# EDR.net
KiCad netlist of a schematic drawn in Altium Designer
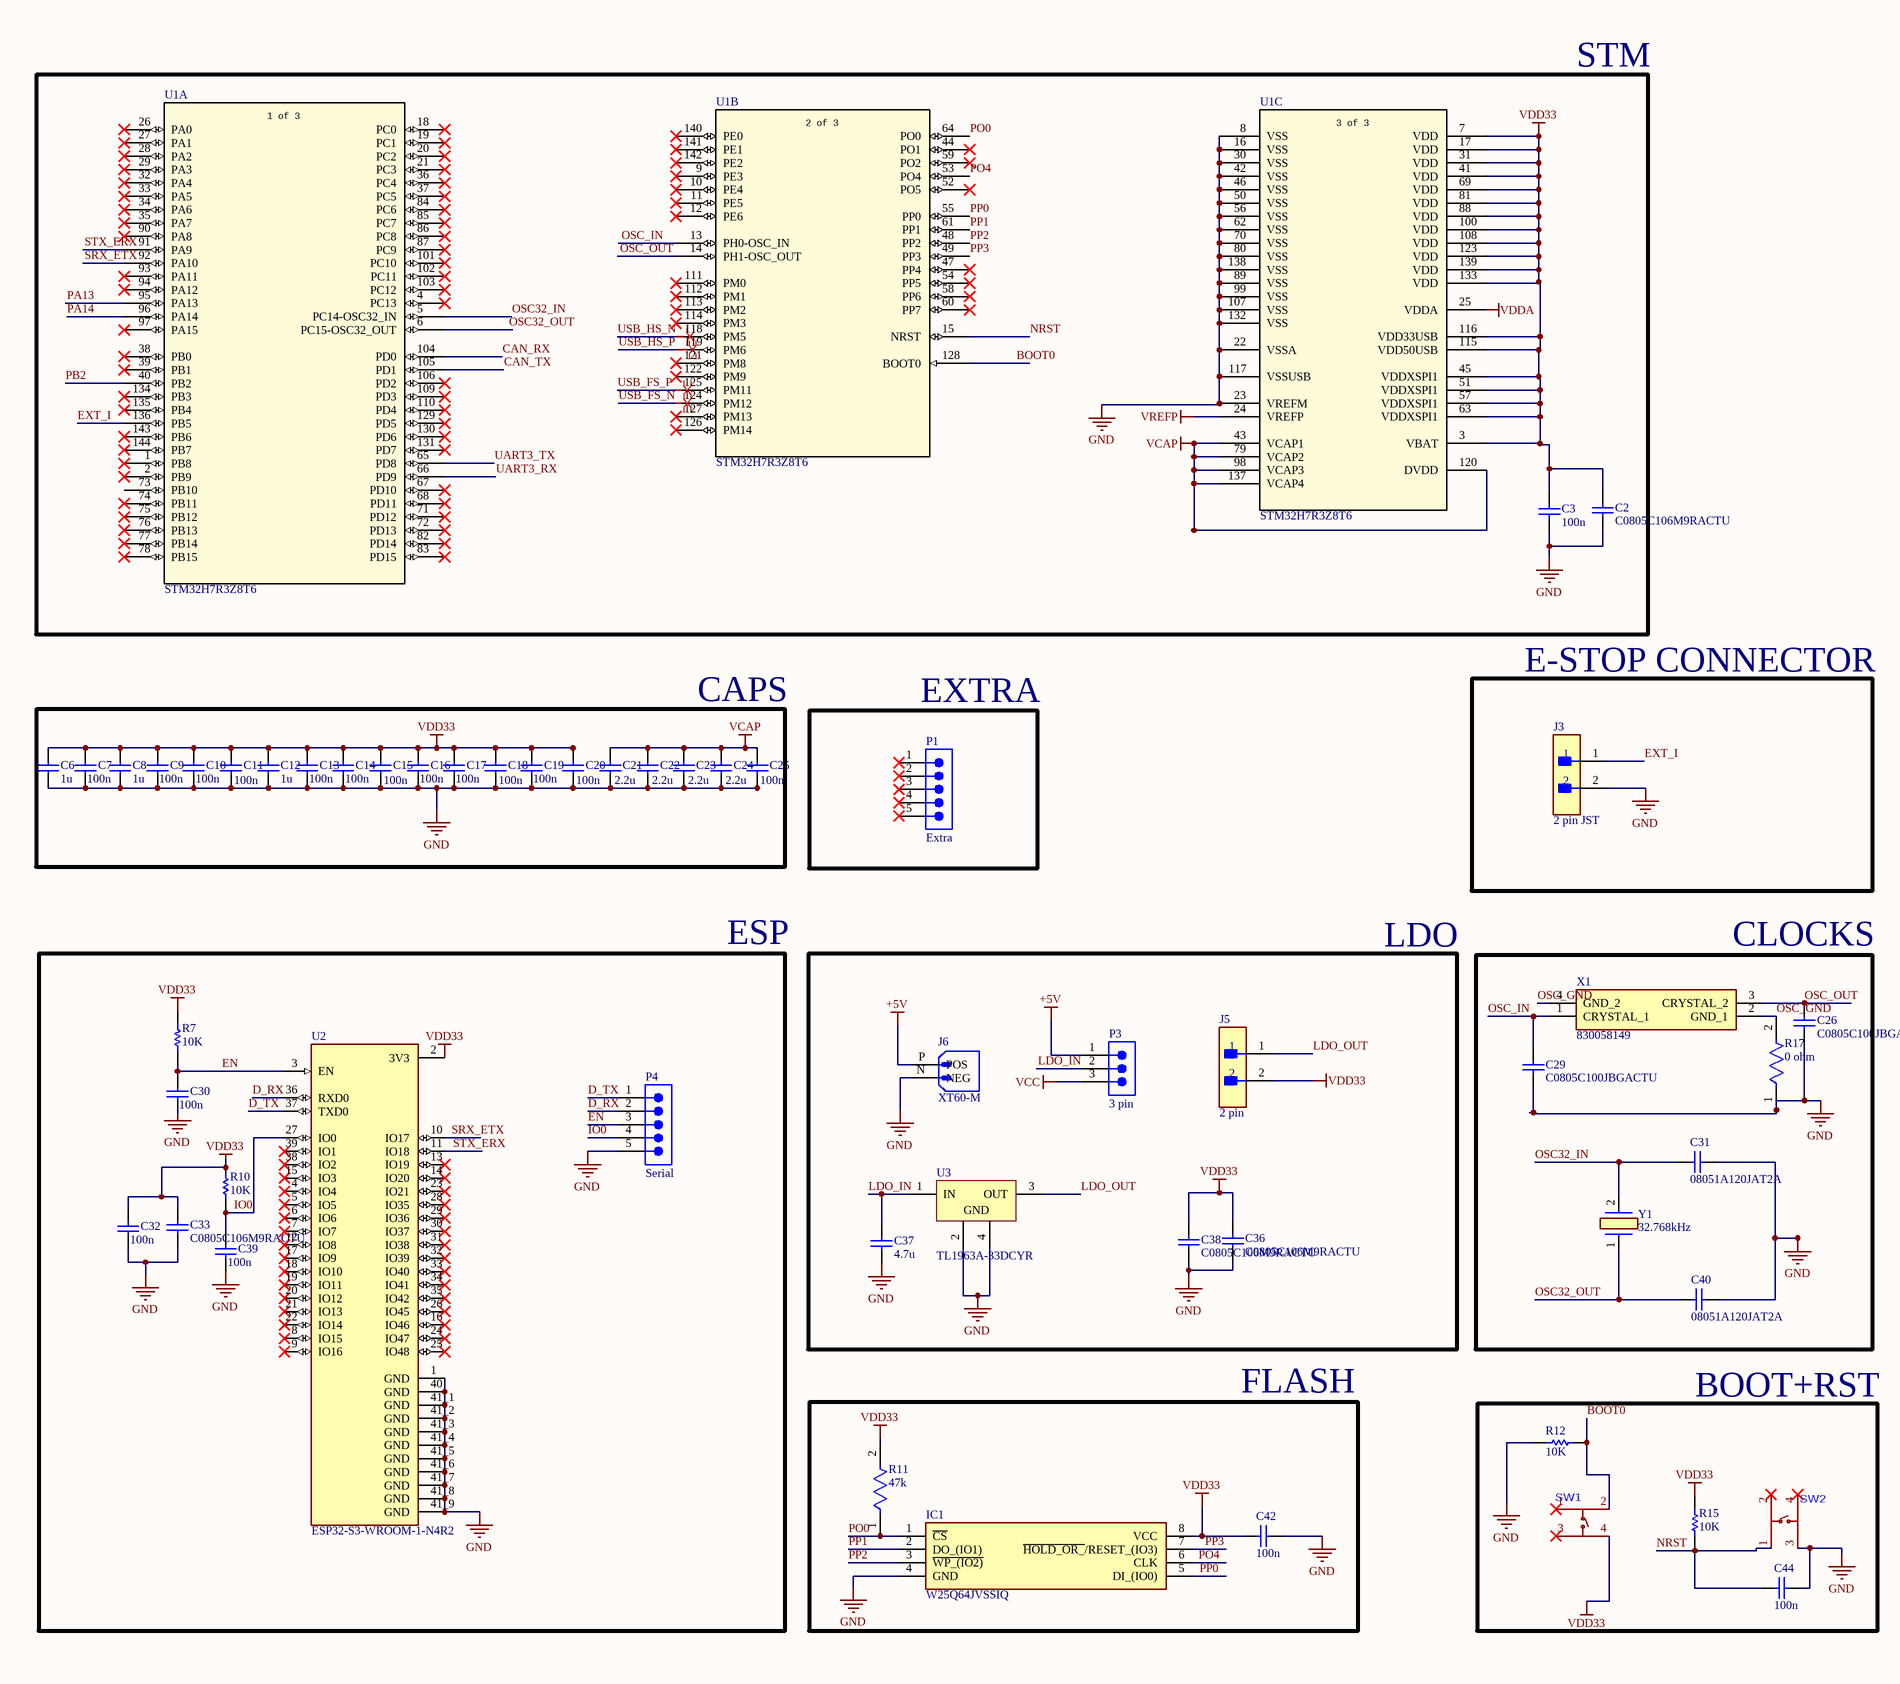
[diagram p0: EDR.SchDoc, left]
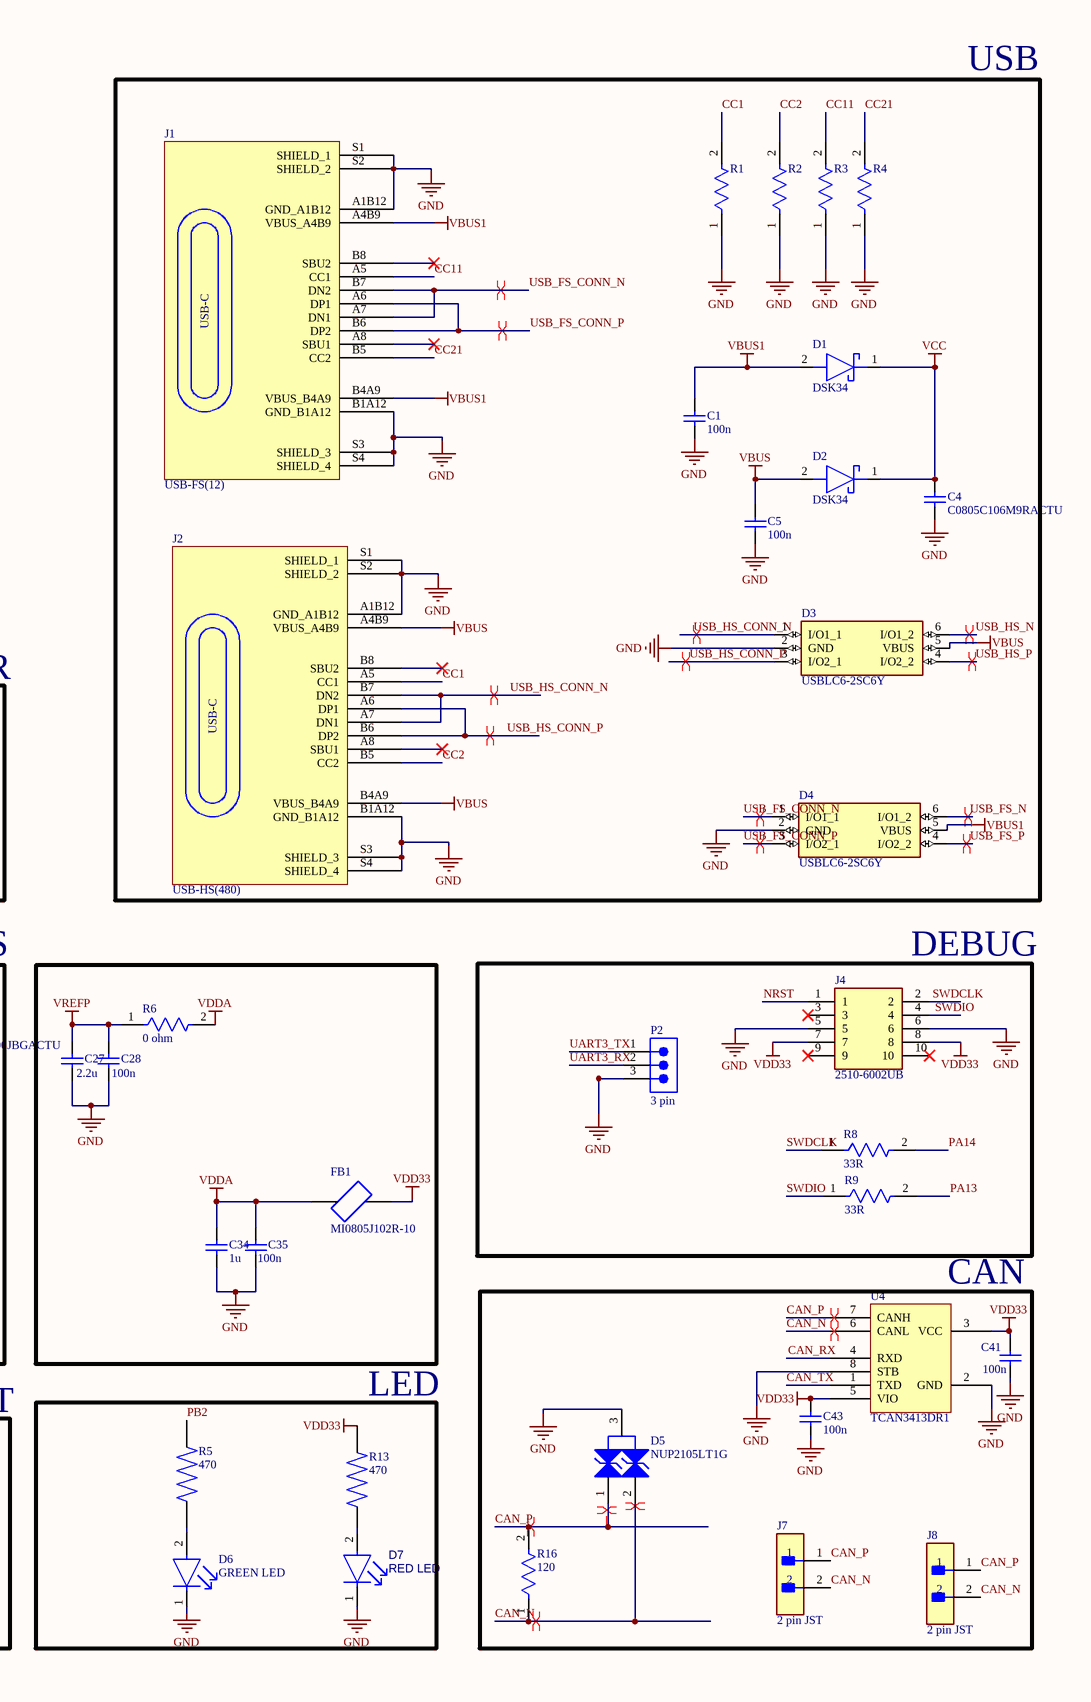
[diagram p1: EDR.SchDoc, right]

(export (version "E")
  (design (tool "Eeschema 10.0.6"))
  (components
    (comp (ref "C1")
      (value "100n")
      (footprint "CAPC2013X145X48ML20T23")
      (description "0.1uF")
      (fields (field (name "PART NUMBER") "VJ0805Y104MXAMT") (field (name "MANUFACTURER") "Vitramon"))
      (libsource (lib "Schlib1") (part "CMP-2007-01796-1"))
    )
    (comp (ref "C2")
      (value "C0805C106M9RACTU")
      (footprint "CAPC2013X145X50ML20T25")
      (description "10uF")
      (fields (field (name "MANUFACTURER") "Kemet") (field (name "LCSC PART NUMBER") "C1710"))
      (libsource (lib "Schlib1") (part "CMP-2007-01213-1"))
    )
    (comp (ref "C3")
      (value "100n")
      (footprint "CAPC2013X145X48ML20T23")
      (description "0.1uF")
      (fields (field (name "PART NUMBER") "VJ0805Y104MXAMT") (field (name "MANUFACTURER") "Vitramon"))
      (libsource (lib "Schlib1") (part "CMP-2007-01796-1"))
    )
    (comp (ref "C4")
      (value "C0805C106M9RACTU")
      (footprint "CAPC2013X145X50ML20T25")
      (description "10uF")
      (fields (field (name "MANUFACTURER") "Kemet") (field (name "LCSC PART NUMBER") "C1710"))
      (libsource (lib "Schlib1") (part "CMP-2007-01213-1"))
    )
    (comp (ref "C5")
      (value "100n")
      (footprint "CAPC2013X145X48ML20T23")
      (description "0.1uF")
      (fields (field (name "PART NUMBER") "VJ0805Y104MXAMT") (field (name "MANUFACTURER") "Vitramon"))
      (libsource (lib "Schlib1") (part "CMP-2007-01796-1"))
    )
    (comp (ref "C6")
      (value "1u")
      (footprint "CAPC2013X145X50ML20T20")
      (description "1uF")
      (fields (field (name "PART NUMBER") "VJ0805Y105KXQRW1BC") (field (name "MANUFACTURER") "Vitramon"))
      (libsource (lib "Schlib1") (part "CMP-2007-01676-1"))
    )
    (comp (ref "C7")
      (value "100n")
      (footprint "CAPC2013X145X48ML20T23")
      (description "0.1uF")
      (fields (field (name "PART NUMBER") "VJ0805Y104MXAMT") (field (name "MANUFACTURER") "Vitramon"))
      (libsource (lib "Schlib1") (part "CMP-2007-01796-1"))
    )
    (comp (ref "C8")
      (value "1u")
      (footprint "CAPC2013X145X50ML20T20")
      (description "1uF")
      (fields (field (name "PART NUMBER") "VJ0805Y105KXQRW1BC") (field (name "MANUFACTURER") "Vitramon"))
      (libsource (lib "Schlib1") (part "CMP-2007-01676-1"))
    )
    (comp (ref "C9")
      (value "100n")
      (footprint "CAPC2013X145X48ML20T23")
      (description "0.1uF")
      (fields (field (name "PART NUMBER") "VJ0805Y104MXAMT") (field (name "MANUFACTURER") "Vitramon"))
      (libsource (lib "Schlib1") (part "CMP-2007-01796-1"))
    )
    (comp (ref "C10")
      (value "100n")
      (footprint "CAPC2013X145X48ML20T23")
      (description "0.1uF")
      (fields (field (name "PART NUMBER") "VJ0805Y104MXAMT") (field (name "MANUFACTURER") "Vitramon"))
      (libsource (lib "Schlib1") (part "CMP-2007-01796-1"))
    )
    (comp (ref "C11")
      (value "100n")
      (footprint "CAPC2013X145X48ML20T23")
      (description "0.1uF")
      (fields (field (name "PART NUMBER") "VJ0805Y104MXAMT") (field (name "MANUFACTURER") "Vitramon"))
      (libsource (lib "Schlib1") (part "CMP-2007-01796-1"))
    )
    (comp (ref "C12")
      (value "1u")
      (footprint "CAPC2013X145X50ML20T20")
      (description "1uF")
      (fields (field (name "PART NUMBER") "VJ0805Y105KXQRW1BC") (field (name "MANUFACTURER") "Vitramon"))
      (libsource (lib "Schlib1") (part "CMP-2007-01676-1"))
    )
    (comp (ref "C13")
      (value "100n")
      (footprint "CAPC2013X145X48ML20T23")
      (description "0.1uF")
      (fields (field (name "PART NUMBER") "VJ0805Y104MXAMT") (field (name "MANUFACTURER") "Vitramon"))
      (libsource (lib "Schlib1") (part "CMP-2007-01796-1"))
    )
    (comp (ref "C14")
      (value "100n")
      (footprint "CAPC2013X145X48ML20T23")
      (description "0.1uF")
      (fields (field (name "PART NUMBER") "VJ0805Y104MXAMT") (field (name "MANUFACTURER") "Vitramon"))
      (libsource (lib "Schlib1") (part "CMP-2007-01796-1"))
    )
    (comp (ref "C15")
      (value "100n")
      (footprint "CAPC2013X145X48ML20T23")
      (description "0.1uF")
      (fields (field (name "PART NUMBER") "VJ0805Y104MXAMT") (field (name "MANUFACTURER") "Vitramon"))
      (libsource (lib "Schlib1") (part "CMP-2007-01796-1"))
    )
    (comp (ref "C16")
      (value "100n")
      (footprint "CAPC2013X145X48ML20T23")
      (description "0.1uF")
      (fields (field (name "PART NUMBER") "VJ0805Y104MXAMT") (field (name "MANUFACTURER") "Vitramon"))
      (libsource (lib "Schlib1") (part "CMP-2007-01796-1"))
    )
    (comp (ref "C17")
      (value "100n")
      (footprint "CAPC2013X145X48ML20T23")
      (description "0.1uF")
      (fields (field (name "PART NUMBER") "VJ0805Y104MXAMT") (field (name "MANUFACTURER") "Vitramon"))
      (libsource (lib "Schlib1") (part "CMP-2007-01796-1"))
    )
    (comp (ref "C18")
      (value "100n")
      (footprint "CAPC2013X145X48ML20T23")
      (description "0.1uF")
      (fields (field (name "PART NUMBER") "VJ0805Y104MXAMT") (field (name "MANUFACTURER") "Vitramon"))
      (libsource (lib "Schlib1") (part "CMP-2007-01796-1"))
    )
    (comp (ref "C19")
      (value "100n")
      (footprint "CAPC2013X145X48ML20T23")
      (description "0.1uF")
      (fields (field (name "PART NUMBER") "VJ0805Y104MXAMT") (field (name "MANUFACTURER") "Vitramon"))
      (libsource (lib "Schlib1") (part "CMP-2007-01796-1"))
    )
    (comp (ref "C20")
      (value "100n")
      (footprint "CAPC2013X145X48ML20T23")
      (description "0.1uF")
      (fields (field (name "PART NUMBER") "VJ0805Y104MXAMT") (field (name "MANUFACTURER") "Vitramon"))
      (libsource (lib "Schlib1") (part "CMP-2007-01796-1"))
    )
    (comp (ref "C21")
      (value "2.2u")
      (footprint "CAPC2013X140X50ML20T25")
      (description "2.2uF")
      (fields (field (name "PART NUMBER") "C0805X225K8RACTU") (field (name "MANUFACTURER") "Kemet"))
      (libsource (lib "Schlib1") (part "CMP-2007-03314-1"))
    )
    (comp (ref "C22")
      (value "2.2u")
      (footprint "CAPC2013X140X50ML20T25")
      (description "2.2uF")
      (fields (field (name "PART NUMBER") "C0805X225K8RACTU") (field (name "MANUFACTURER") "Kemet"))
      (libsource (lib "Schlib1") (part "CMP-2007-03314-1"))
    )
    (comp (ref "C23")
      (value "2.2u")
      (footprint "CAPC2013X140X50ML20T25")
      (description "2.2uF")
      (fields (field (name "PART NUMBER") "C0805X225K8RACTU") (field (name "MANUFACTURER") "Kemet"))
      (libsource (lib "Schlib1") (part "CMP-2007-03314-1"))
    )
    (comp (ref "C24")
      (value "2.2u")
      (footprint "CAPC2013X140X50ML20T25")
      (description "2.2uF")
      (fields (field (name "PART NUMBER") "C0805X225K8RACTU") (field (name "MANUFACTURER") "Kemet"))
      (libsource (lib "Schlib1") (part "CMP-2007-03314-1"))
    )
    (comp (ref "C25")
      (value "100n")
      (footprint "CAPC2013X145X48ML20T23")
      (description "0.1uF")
      (fields (field (name "PART NUMBER") "VJ0805Y104MXAMT") (field (name "MANUFACTURER") "Vitramon"))
      (libsource (lib "Schlib1") (part "CMP-2007-01796-1"))
    )
    (comp (ref "C26")
      (value "C0805C100JBGACTU")
      (footprint "CAPC1608X92X38NL15T08")
      (description "10pF")
      (fields (field (name "MANUFACTURER") "Kemet") (field (name "LCSC PART NUMBER") "C1710"))
      (libsource (lib "Schlib1") (part "CMP-2007-03323-1"))
    )
    (comp (ref "C27")
      (value "2.2u")
      (footprint "CAPC2013X140X50ML20T25")
      (description "2.2uF")
      (fields (field (name "PART NUMBER") "C0805X225K8RACTU") (field (name "MANUFACTURER") "Kemet"))
      (libsource (lib "Schlib1") (part "CMP-2007-03314-1"))
    )
    (comp (ref "C28")
      (value "100n")
      (footprint "CAPC2013X145X48ML20T23")
      (description "0.1uF")
      (fields (field (name "PART NUMBER") "VJ0805Y104MXAMT") (field (name "MANUFACTURER") "Vitramon"))
      (libsource (lib "Schlib1") (part "CMP-2007-01796-1"))
    )
    (comp (ref "C29")
      (value "C0805C100JBGACTU")
      (footprint "CAPC1608X92X38NL15T08")
      (description "10pF")
      (fields (field (name "MANUFACTURER") "Kemet") (field (name "LCSC PART NUMBER") "C1710"))
      (libsource (lib "Schlib1") (part "CMP-2007-03323-1"))
    )
    (comp (ref "C30")
      (value "100n")
      (footprint "CAPC2013X145X48ML20T23")
      (description "0.1uF")
      (fields (field (name "PART NUMBER") "VJ0805Y104MXAMT") (field (name "MANUFACTURER") "Vitramon"))
      (libsource (lib "Schlib1") (part "CMP-2007-01796-1"))
    )
    (comp (ref "C31")
      (value "08051A120JAT2A")
      (footprint "CAPC1608X92X38NL15T08")
      (description "7pF")
      (fields
        (field (name "MANUFACTURER") "AVX Interconnect / Elco")
        (field (name "LCSC PART NUMBER") "C136031")
      )
      (libsource (lib "Schlib1") (part "CMP-2007-04128-1"))
    )
    (comp (ref "C32")
      (value "100n")
      (footprint "CAPC2013X145X48ML20T23")
      (description "0.1uF")
      (fields (field (name "PART NUMBER") "VJ0805Y104MXAMT") (field (name "MANUFACTURER") "Vitramon"))
      (libsource (lib "Schlib1") (part "CMP-2007-01796-1"))
    )
    (comp (ref "C33")
      (value "C0805C106M9RACTU")
      (footprint "CAPC2013X145X50ML20T25")
      (description "10uF")
      (fields (field (name "MANUFACTURER") "Kemet") (field (name "LCSC PART NUMBER") "C1710"))
      (libsource (lib "Schlib1") (part "CMP-2007-01213-1"))
    )
    (comp (ref "C34")
      (value "1u")
      (footprint "CAPC2013X145X50ML20T20")
      (description "1uF")
      (fields (field (name "PART NUMBER") "VJ0805Y105KXQRW1BC") (field (name "MANUFACTURER") "Vitramon"))
      (libsource (lib "Schlib1") (part "CMP-2007-01676-1"))
    )
    (comp (ref "C35")
      (value "100n")
      (footprint "CAPC2013X145X48ML20T23")
      (description "0.1uF")
      (fields (field (name "PART NUMBER") "VJ0805Y104MXAMT") (field (name "MANUFACTURER") "Vitramon"))
      (libsource (lib "Schlib1") (part "CMP-2007-01796-1"))
    )
    (comp (ref "C36")
      (value "C0805C106M9RACTU")
      (footprint "CAPC2013X145X50ML20T25")
      (description "10uF")
      (fields (field (name "MANUFACTURER") "Kemet") (field (name "LCSC PART NUMBER") "C1710"))
      (libsource (lib "Schlib1") (part "CMP-2007-01213-1"))
    )
    (comp (ref "C37")
      (value "4.7u")
      (footprint "CAPC2013X145X50ML20T25")
      (description "4.7uF")
      (fields (field (name "PART NUMBER") "C0805C475K9RACTU") (field (name "MANUFACTURER") "Kemet"))
      (libsource (lib "Schlib1") (part "CMP-2007-01189-1"))
    )
    (comp (ref "C38")
      (value "C0805C106M9RACTU")
      (footprint "CAPC2013X145X50ML20T25")
      (description "10uF")
      (fields (field (name "MANUFACTURER") "Kemet") (field (name "LCSC PART NUMBER") "C1710"))
      (libsource (lib "Schlib1") (part "CMP-2007-01213-1"))
    )
    (comp (ref "C39")
      (value "100n")
      (footprint "CAPC2013X145X48ML20T23")
      (description "0.1uF")
      (fields (field (name "PART NUMBER") "VJ0805Y104MXAMT") (field (name "MANUFACTURER") "Vitramon"))
      (libsource (lib "Schlib1") (part "CMP-2007-01796-1"))
    )
    (comp (ref "C40")
      (value "08051A120JAT2A")
      (footprint "CAPC1608X92X38NL15T08")
      (description "7pF")
      (fields
        (field (name "MANUFACTURER") "AVX Interconnect / Elco")
        (field (name "LCSC PART NUMBER") "C136031")
      )
      (libsource (lib "Schlib1") (part "CMP-2007-04128-1"))
    )
    (comp (ref "C41")
      (value "100n")
      (footprint "CAPC2013X145X48ML20T23")
      (description "0.1uF")
      (fields (field (name "PART NUMBER") "VJ0805Y104MXAMT") (field (name "MANUFACTURER") "Vitramon"))
      (libsource (lib "Schlib1") (part "CMP-2007-01796-1"))
    )
    (comp (ref "C42")
      (value "100n")
      (footprint "CAPC2013X145X48ML20T23")
      (description "0.1uF")
      (fields (field (name "PART NUMBER") "VJ0805Y104MXAMT") (field (name "MANUFACTURER") "Vitramon"))
      (libsource (lib "Schlib1") (part "CMP-2007-01796-1"))
    )
    (comp (ref "C43")
      (value "100n")
      (footprint "CAPC2013X145X48ML20T23")
      (description "0.1uF")
      (fields (field (name "PART NUMBER") "VJ0805Y104MXAMT") (field (name "MANUFACTURER") "Vitramon"))
      (libsource (lib "Schlib1") (part "CMP-2007-01796-1"))
    )
    (comp (ref "C44")
      (value "100n")
      (footprint "CAPC2013X145X48ML20T23")
      (description "0.1uF")
      (fields (field (name "PART NUMBER") "VJ0805Y104MXAMT") (field (name "MANUFACTURER") "Vitramon"))
      (libsource (lib "Schlib1") (part "CMP-2007-01796-1"))
    )
    (comp (ref "D1")
      (value "DSK34")
      (footprint "SamacSys:SODFL3818X130N")
      (description "Schottky Diode")
      (fields (field (name "LCSC PART NUMBER") "C41371066"))
      (libsource (lib "Schlib1") (part "DSK34"))
    )
    (comp (ref "D2")
      (value "DSK34")
      (footprint "SamacSys:SODFL3818X130N")
      (description "Schottky Diode")
      (fields (field (name "LCSC PART NUMBER") "C41371066"))
      (libsource (lib "Schlib1") (part "DSK34"))
    )
    (comp (ref "D3")
      (value "USBLC6-2SC6Y")
      (footprint "SOT95P280X145-6N")
      (description "17V Clamp 5A (8/20µs) Ipp Tvs Diode Surface Mount SOT-23-6")
      (fields (field (name "LCSC PART #") "C2969755") (field (name "MF") "STMicroelectronics"))
      (libsource (lib "Schlib1") (part "USBLC6-2SC6Y"))
    )
    (comp (ref "D4")
      (value "USBLC6-2SC6Y")
      (footprint "SOT95P280X145-6N")
      (description "17V Clamp 5A (8/20µs) Ipp Tvs Diode Surface Mount SOT-23-6")
      (fields (field (name "LCSC PART #") "C2969755") (field (name "MF") "STMicroelectronics"))
      (libsource (lib "Schlib1") (part "USBLC6-2SC6Y"))
    )
    (comp (ref "D5")
      (value "NUP2105LT1G")
      (footprint "ONSC-SOT-23-3-318-08_V")
      (description "Dual Line CAN Bus Protector, 3-Pin SOT-23, Pb-Free, Tape and Reel")
      (fields (field (name "MANUFACTURER") "On Semiconductor") (field (name "LCSC PART NUMBER") "C14486"))
      (libsource (lib "Schlib1") (part "CMP-1063-00164-1"))
    )
    (comp (ref "D6")
      (value "GREEN LED")
      (footprint "FP-SML-210-MFG")
      (description "LED GREEN CLEAR 0805 SMD")
      (fields (field (name "MANUFACTURER PART NUMBER") "SML-210MTT86") (field (name "MANUFACTURER") "ROHM"))
      (libsource (lib "Schlib1") (part "CMP-08952-000013-1"))
    )
    (comp (ref "D7")
      (value "RED LED")
      (footprint "LED_APHCM2012SURCK-F01")
      (fields (field (name "LCSC PART NUMBER") "C19171391") (field (name "MANUFACTURER") "KINGBRIGHT"))
      (libsource (lib "Schlib1") (part "LED_RED_KINGBRIGHT"))
    )
    (comp (ref "FB1")
      (value "MI0805J102R-10")
      (footprint "FB_MI0805J102R-10")
      (fields
        (field (name "MF") "Laird-Signal Integrity Products")
        (field (name "LCSC PART NUMBER") "C85835")
      )
      (libsource (lib "Schlib1") (part "MI0805J102R-10"))
    )
    (comp (ref "IC1")
      (value "W25Q64JVSSIQ")
      (footprint "SamacSys:SOIC127P790X216-8N")
      (description "Integrated Circuit")
      (fields
        (field (name "MOUSER PART NUMBER") "454-W25Q64JVSSIQ")
        (field (name "LCSC PART NUMBER") "C179171")
      )
      (libsource (lib "Schlib1") (part "W25Q64JVSSIQ"))
    )
    (comp (ref "J1")
      (value "USB-FS(12)")
      (footprint "FP-2171790001-MFG")
      (description "CONN RCP USB2.0 TYP C 24P SMD RA")
      (fields (field (name "MANUFACTURER") "Molex") (field (name "MANUFACTURER PART NUMBER") "217179-0001"))
      (libsource (lib "Schlib1") (part "217179-0001"))
    )
    (comp (ref "J2")
      (value "USB-HS(480)")
      (footprint "FP-2171790001-MFG")
      (description "CONN RCP USB2.0 TYP C 24P SMD RA")
      (fields (field (name "MANUFACTURER") "Molex") (field (name "MANUFACTURER PART NUMBER") "217179-0001"))
      (libsource (lib "Schlib1") (part "217179-0001"))
    )
    (comp (ref "J3")
      (value "2 pin JST")
      (footprint "FP-B2B-XH-A_LF_SN-MFG")
      (description "CONN HEADER VERT 2POS 2.5MM")
      (fields (field (name "LCSC PART NUMBER") "C19271386"))
      (libsource (lib "Schlib1") (part "CMP-2000-05888-3"))
    )
    (comp (ref "J4")
      (value "2510-6002UB")
      (footprint "PcbLib1:SHDR10W64P254_2X5_2002X859X991P")
      (description "10 Pin Connector")
      (fields (field (name "MOUSER PART NUMBER") "517-2510-6002"))
      (libsource (lib "Schlib1") (part "2510-6002UB"))
    )
    (comp (ref "J5")
      (value "2 pin")
      (footprint "FP-TSW-102-07-F-S-MFG")
      (description "CONN HEADER VERT 2POS 2.54MM")
      (libsource (lib "Schlib1") (part "CMP-02766-001458-1"))
    )
    (comp (ref "J6")
      (value "XT60-M")
      (footprint "AMASS_XT60-M")
      (description "Plug; DC supply; XT60; male; PIN: 2; for cable; soldered; 30A; 500V")
      (fields (field (name "MF") "AMASS"))
      (libsource (lib "Schlib1") (part "XT60-M"))
    )
    (comp (ref "J7")
      (value "2 pin JST")
      (footprint "FP-B2B-XH-A_LF_SN-MFG")
      (description "CONN HEADER VERT 2POS 2.5MM")
      (fields (field (name "LCSC PART NUMBER") "C19271386"))
      (libsource (lib "Schlib1") (part "CMP-2000-05888-3"))
    )
    (comp (ref "J8")
      (value "2 pin JST")
      (footprint "FP-B2B-XH-A_LF_SN-MFG")
      (description "CONN HEADER VERT 2POS 2.5MM")
      (fields (field (name "LCSC PART NUMBER") "C19271386"))
      (libsource (lib "Schlib1") (part "CMP-2000-05888-3"))
    )
    (comp (ref "P1")
      (value "Extra")
      (footprint "61300511121")
      (description "THT Vertical Pin Header WR-PHD, Pitch 2.54 mm, Single Row, 5 pins")
      (libsource (lib "Schlib1") (part "CMP-1502-01068-4"))
    )
    (comp (ref "P2")
      (value "3 pin")
      (footprint "61300311121")
      (description "THT Vertical Pin Header WR-PHD, Pitch 2.54 mm, Single Row, 3 pins")
      (libsource (lib "Schlib1") (part "CMP-1502-01062-4"))
    )
    (comp (ref "P3")
      (value "3 pin")
      (footprint "61300311121")
      (description "THT Vertical Pin Header WR-PHD, Pitch 2.54 mm, Single Row, 3 pins")
      (libsource (lib "Schlib1") (part "CMP-1502-01062-4"))
    )
    (comp (ref "P4")
      (value "Serial")
      (footprint "61300511121")
      (description "THT Vertical Pin Header WR-PHD, Pitch 2.54 mm, Single Row, 5 pins")
      (libsource (lib "Schlib1") (part "CMP-1502-01068-4"))
    )
    (comp (ref "R1")
      (value "~")
      (footprint "FP-AC0805-IPC_B")
      (description "RES SMD 5.1K OHM 5% 1/2W 0805")
      (fields
        (field (name "OCTOPART") "https://octopart.com/ac0805jr-075k1l-yageo-21711115")
        (field (name "MANUFACTURER") "Yageo")
      )
      (libsource (lib "Schlib1") (part "CMP-2001-04477-2"))
    )
    (comp (ref "R2")
      (value "~")
      (footprint "FP-AC0805-IPC_B")
      (description "RES SMD 5.1K OHM 5% 1/2W 0805")
      (fields
        (field (name "OCTOPART") "https://octopart.com/ac0805jr-075k1l-yageo-21711115")
        (field (name "MANUFACTURER") "Yageo")
      )
      (libsource (lib "Schlib1") (part "CMP-2001-04477-2"))
    )
    (comp (ref "R3")
      (value "~")
      (footprint "FP-AC0805-IPC_B")
      (description "RES SMD 5.1K OHM 5% 1/2W 0805")
      (fields
        (field (name "OCTOPART") "https://octopart.com/ac0805jr-075k1l-yageo-21711115")
        (field (name "MANUFACTURER") "Yageo")
      )
      (libsource (lib "Schlib1") (part "CMP-2001-04477-2"))
    )
    (comp (ref "R4")
      (value "~")
      (footprint "FP-AC0805-IPC_B")
      (description "RES SMD 5.1K OHM 5% 1/2W 0805")
      (fields
        (field (name "OCTOPART") "https://octopart.com/ac0805jr-075k1l-yageo-21711115")
        (field (name "MANUFACTURER") "Yageo")
      )
      (libsource (lib "Schlib1") (part "CMP-2001-04477-2"))
    )
    (comp (ref "R5")
      (value "470")
      (footprint "RESC2012X65N")
      (description "Fixed Resistor CRGCQ 0805 470R 5%")
      (fields (field (name "MF") "TE Connectivity") (field (name "MP") "CRGCQ0805J470R"))
      (libsource (lib "Schlib1") (part "CRGCQ0805J470R"))
    )
    (comp (ref "R6")
      (value "0 ohm")
      (footprint "FP-HCJ0805-IPC_B")
      (description "RES 0 OHM JUMPER 1/2W 0805")
      (libsource (lib "Schlib1") (part "CMP-26527-000104-1"))
    )
    (comp (ref "R7")
      (value "10K")
      (footprint "RESC0805(2012)_M")
      (description "10K 0.5W 5% 0805 (2012 Metric)  SMD")
      (fields (field (name "POWER") "0.5W") (field (name "TOLERANCE") "5 %"))
      (libsource (lib "Schlib1") (part "CMP-1013-00098-1"))
    )
    (comp (ref "R8")
      (value "33R")
      (footprint "FP-AC0805-IPC_B")
      (description "RES SMD 33 OHM 1% 1/8W 0805")
      (fields
        (field (name "OCTOPART") "https://octopart.com/ac0805fr-0733rl-yageo-46503501")
        (field (name "MANUFACTURER") "Yageo")
      )
      (libsource (lib "Schlib1") (part "CMP-03412-037241-1"))
    )
    (comp (ref "R9")
      (value "33R")
      (footprint "FP-AC0805-IPC_B")
      (description "RES SMD 33 OHM 1% 1/8W 0805")
      (fields
        (field (name "OCTOPART") "https://octopart.com/ac0805fr-0733rl-yageo-46503501")
        (field (name "MANUFACTURER") "Yageo")
      )
      (libsource (lib "Schlib1") (part "CMP-03412-037241-1"))
    )
    (comp (ref "R10")
      (value "10K")
      (footprint "RESC0805(2012)_M")
      (description "10K 0.5W 5% 0805 (2012 Metric)  SMD")
      (fields (field (name "POWER") "0.5W") (field (name "TOLERANCE") "5 %"))
      (libsource (lib "Schlib1") (part "CMP-1013-00098-1"))
    )
    (comp (ref "R11")
      (value "47k")
      (footprint "FP-CRCW0805-e3-IPC_B")
      (description "RES Thick Film, 47kΩ, 1%, 0.5W, 100ppm/°C, 0805")
      (fields (field (name "TOLERANCE") "1%") (field (name "LCSC PART NUMBER") "C441957"))
      (libsource (lib "Schlib1") (part "CMP-02407-012789-1"))
    )
    (comp (ref "R12")
      (value "10K")
      (footprint "RESC0805(2012)_M")
      (description "10K 0.5W 5% 0805 (2012 Metric)  SMD")
      (fields (field (name "POWER") "0.5W") (field (name "TOLERANCE") "5 %"))
      (libsource (lib "Schlib1") (part "CMP-1013-00098-1"))
    )
    (comp (ref "R13")
      (value "470")
      (footprint "RESC2012X65N")
      (description "Fixed Resistor CRGCQ 0805 470R 5%")
      (fields (field (name "MF") "TE Connectivity") (field (name "MP") "CRGCQ0805J470R"))
      (libsource (lib "Schlib1") (part "CRGCQ0805J470R"))
    )
    (comp (ref "R15")
      (value "10K")
      (footprint "RESC0805(2012)_M")
      (description "10K 0.5W 5% 0805 (2012 Metric)  SMD")
      (fields (field (name "POWER") "0.5W") (field (name "TOLERANCE") "5 %"))
      (libsource (lib "Schlib1") (part "CMP-1013-00098-1"))
    )
    (comp (ref "R16")
      (value "120")
      (footprint "FP-RMCF0805-IPC_B")
      (description "120Ω ±5% 0.5W 0805 Thick Film Chip Resistor AEC-Q200 compliant")
      (fields (field (name "TOLERANCE") "5%") (field (name "LCSC PART NUMBER") "C410053"))
      (libsource (lib "Schlib1") (part "CMP-26527-002953-1"))
    )
    (comp (ref "R17")
      (value "0 ohm")
      (footprint "FP-HCJ0805-IPC_B")
      (description "RES 0 OHM JUMPER 1/2W 0805")
      (libsource (lib "Schlib1") (part "CMP-26527-000104-1"))
    )
    (comp (ref "SW1")
      (value "4.5X4.5X5.0WATERPROOF TACT SWITCH DIP 260G")
      (footprint "SW-TH_4P-L4.5-W4.5-P3.00-LS5.5 - duplicate")
      (description "SMD Switch")
      (fields (field (name "LCSC PART NUMBER") "C39832249"))
      (libsource (lib "Schlib1") (part "4.5X4.5X5.0WATERPROOF TACT SWITCH DIP 260G"))
    )
    (comp (ref "SW2")
      (value "4.5X4.5X5.0WATERPROOF TACT SWITCH DIP 260G")
      (footprint "SW-TH_4P-L4.5-W4.5-P3.00-LS5.5 - duplicate")
      (description "SMD Switch")
      (fields (field (name "LCSC PART NUMBER") "C39832249"))
      (libsource (lib "Schlib1") (part "4.5X4.5X5.0WATERPROOF TACT SWITCH DIP 260G"))
    )
    (comp (ref "U1")
      (value "STM32H7R3Z8T6")
      (footprint "LQFP-144_STM-M")
      (fields
        (field (name "LCSC PART NUMBER") "C26125147")
        (field (name "COPYRIGHT") "Copyright (C) 2025 Ultra Librarian. All rights reserved.")
      )
      (libsource (lib "Schlib1") (part "STM32H7R3Z8T6"))
    )
    (comp (ref "U2")
      (value "ESP32-S3-WROOM-1-N4R2")
      (footprint "XCVR_ESP32-S3-WROOM-1-N4R2")
      (description "Bluetooth, WiFi 802.11b/g/n, Bluetooth v5.0 Transceiver Module 2.4GHz PCB Trace Surface Mount")
      (fields (field (name "MF") "Espressif Systems") (field (name "LCSC PART NUMBER") "C82899"))
      (libsource (lib "Schlib1") (part "ESP32-S3-WROOM-1-N4R2"))
    )
    (comp (ref "U3")
      (value "TL1963A-33DCYR")
      (footprint "DCY0004A_L")
      (fields (field (name "MANUFACTURER") "Texas Instruments") (field (name "LCSC PART NUMBER") "C181262"))
      (libsource (lib "Schlib1") (part "CMP-0395-00535-2"))
    )
    (comp (ref "U4")
      (value "TCAN3413DR1")
      (footprint "TCAN3413DR1")
      (description "CAN Transciever")
      (fields (field (name "LCSC PART NUMBER") "C22396693"))
      (libsource (lib "Schlib1") (part "TCAN3413DR1"))
    )
    (comp (ref "X1")
      (value "830058149")
      (footprint "830058149-x1")
      (fields
        (field (name "MOUSER PART NUMBER") "710-830058149")
        (field (name "LCSC PART NUMBER") "C20617576")
      )
      (libsource (lib "Schlib1") (part "830058149"))
    )
    (comp (ref "Y1")
      (value "32.768kHz")
      (footprint "SamacSys:CM7V32768TBQA020")
      (description "Crystal or Oscillator")
      (fields
        (field (name "MANUFACTURER_PART_NUMBER") "CM7V-T1A-32.768KHZ-7PF-10PPM-TA-QC")
        (field (name "MOUSER PART NUMBER") "428-201563-MG01")
      )
      (libsource (lib "Schlib1") (part "CM7V-T1A-32.768KHZ-7PF-10PPM-TA-QC"))
    )
  )
  (nets
    (net (code "1") (name "+5V") (class "Default")
      (node (ref "J6") (pin "P") (pinfunction "POS_P") (pintype "passive"))
      (node (ref "P3") (pin "1") (pinfunction "1_1") (pintype "passive"))
    )
    (net (code "2") (name "/BOOT0") (class "Default")
      (node (ref "R12") (pin "2") (pinfunction "2_2") (pintype "passive"))
      (node (ref "SW1") (pin "2") (pinfunction "B_2") (pintype "passive"))
      (node (ref "U1") (pin "128") (pinfunction "BOOT0_128") (pintype "input"))
    )
    (net (code "3") (name "/CAN_N") (class "Default")
      (node (ref "D5") (pin "2") (pinfunction "K_2") (pintype "passive"))
      (node (ref "J7") (pin "2") (pinfunction "2_2") (pintype "passive"))
      (node (ref "J8") (pin "2") (pinfunction "2_2") (pintype "passive"))
      (node (ref "R16") (pin "1") (pinfunction "1_1") (pintype "passive"))
      (node (ref "U4") (pin "6") (pinfunction "CANL_6") (pintype "passive"))
    )
    (net (code "4") (name "/CAN_P") (class "Default")
      (node (ref "D5") (pin "1") (pinfunction "K_1") (pintype "passive"))
      (node (ref "J7") (pin "1") (pinfunction "1_1") (pintype "passive"))
      (node (ref "J8") (pin "1") (pinfunction "1_1") (pintype "passive"))
      (node (ref "R16") (pin "2") (pinfunction "2_2") (pintype "passive"))
      (node (ref "U4") (pin "7") (pinfunction "CANH_7") (pintype "passive"))
    )
    (net (code "5") (name "/CAN_RX") (class "Default")
      (node (ref "U1") (pin "104") (pinfunction "PD0_104") (pintype "bidirectional"))
      (node (ref "U4") (pin "4") (pinfunction "RXD_4") (pintype "passive"))
    )
    (net (code "6") (name "/CAN_TX") (class "Default")
      (node (ref "U1") (pin "105") (pinfunction "PD1_105") (pintype "bidirectional"))
      (node (ref "U4") (pin "1") (pinfunction "TXD_1") (pintype "passive"))
    )
    (net (code "7") (name "/CC1") (class "Default")
      (node (ref "J2") (pin "A5") (pinfunction "CC1_A5") (pintype "passive"))
      (node (ref "R1") (pin "2") (pinfunction "2_2") (pintype "passive"))
    )
    (net (code "8") (name "/CC2") (class "Default")
      (node (ref "J2") (pin "B5") (pinfunction "CC2_B5") (pintype "passive"))
      (node (ref "R2") (pin "2") (pinfunction "2_2") (pintype "passive"))
    )
    (net (code "9") (name "/CC11") (class "Default")
      (node (ref "J1") (pin "A5") (pinfunction "CC1_A5") (pintype "passive"))
      (node (ref "R3") (pin "2") (pinfunction "2_2") (pintype "passive"))
    )
    (net (code "10") (name "/CC21") (class "Default")
      (node (ref "J1") (pin "B5") (pinfunction "CC2_B5") (pintype "passive"))
      (node (ref "R4") (pin "2") (pinfunction "2_2") (pintype "passive"))
    )
    (net (code "11") (name "/D_RX") (class "Default")
      (node (ref "P4") (pin "2") (pinfunction "2_2") (pintype "passive"))
      (node (ref "U2") (pin "36") (pinfunction "RXD0_36") (pintype "bidirectional"))
    )
    (net (code "12") (name "/D_TX") (class "Default")
      (node (ref "P4") (pin "1") (pinfunction "1_1") (pintype "passive"))
      (node (ref "U2") (pin "37") (pinfunction "TXD0_37") (pintype "bidirectional"))
    )
    (net (code "13") (name "/EN") (class "Default")
      (node (ref "C30") (pin "2") (pinfunction "2_2") (pintype "passive"))
      (node (ref "P4") (pin "3") (pinfunction "3_3") (pintype "passive"))
      (node (ref "R7") (pin "2") (pinfunction "2_2") (pintype "passive"))
      (node (ref "U2") (pin "3") (pinfunction "EN_3") (pintype "input"))
    )
    (net (code "14") (name "/EXT_I") (class "Default")
      (node (ref "J3") (pin "1") (pinfunction "1_1") (pintype "passive"))
      (node (ref "U1") (pin "136") (pinfunction "PB5_136") (pintype "bidirectional"))
    )
    (net (code "15") (name "/IO0") (class "Default")
      (node (ref "C39") (pin "2") (pinfunction "2_2") (pintype "passive"))
      (node (ref "P4") (pin "4") (pinfunction "4_4") (pintype "passive"))
      (node (ref "R10") (pin "2") (pinfunction "2_2") (pintype "passive"))
      (node (ref "U2") (pin "27") (pinfunction "IO0_27") (pintype "bidirectional"))
    )
    (net (code "16") (name "/LDO_IN") (class "Default")
      (node (ref "C37") (pin "1") (pinfunction "1_1") (pintype "passive"))
      (node (ref "P3") (pin "2") (pinfunction "2_2") (pintype "passive"))
      (node (ref "U3") (pin "1") (pinfunction "IN_1") (pintype "power_in"))
    )
    (net (code "17") (name "/LDO_OUT") (class "Default")
      (node (ref "J5") (pin "1") (pinfunction "1_1") (pintype "passive"))
      (node (ref "U3") (pin "3") (pinfunction "OUT_3") (pintype "power_in"))
    )
    (net (code "18") (name "/NRST") (class "Default")
      (node (ref "C44") (pin "2") (pinfunction "2_2") (pintype "passive"))
      (node (ref "J4") (pin "1") (pinfunction "1_1") (pintype "passive"))
      (node (ref "R15") (pin "1") (pinfunction "1_1") (pintype "passive"))
      (node (ref "SW2") (pin "1") (pinfunction "A_1") (pintype "passive"))
      (node (ref "U1") (pin "15") (pinfunction "NRST_15") (pintype "bidirectional"))
    )
    (net (code "19") (name "/OSC32_IN") (class "Default")
      (node (ref "C31") (pin "1") (pinfunction "1_1") (pintype "passive"))
      (node (ref "U1") (pin "5") (pinfunction "PC14-OSC32_IN_5") (pintype "bidirectional"))
      (node (ref "Y1") (pin "2") (pinfunction "2_2") (pintype "passive"))
    )
    (net (code "20") (name "/OSC32_OUT") (class "Default")
      (node (ref "C40") (pin "1") (pinfunction "1_1") (pintype "passive"))
      (node (ref "U1") (pin "6") (pinfunction "PC15-OSC32_OUT_6") (pintype "bidirectional"))
      (node (ref "Y1") (pin "1") (pinfunction "1_1") (pintype "passive"))
    )
    (net (code "21") (name "/OSC_GND") (class "Default")
      (node (ref "R17") (pin "2") (pinfunction "2_2") (pintype "passive"))
      (node (ref "X1") (pin "2") (pinfunction "GND_1_2") (pintype "passive"))
      (node (ref "X1") (pin "4") (pinfunction "GND_2_4") (pintype "passive"))
    )
    (net (code "22") (name "/OSC_IN") (class "Default")
      (node (ref "C29") (pin "2") (pinfunction "2_2") (pintype "passive"))
      (node (ref "U1") (pin "13") (pinfunction "PH0-OSC_IN_13") (pintype "bidirectional"))
      (node (ref "X1") (pin "1") (pinfunction "CRYSTAL_1_1") (pintype "passive"))
    )
    (net (code "23") (name "/OSC_OUT") (class "Default")
      (node (ref "C26") (pin "1") (pinfunction "1_1") (pintype "passive"))
      (node (ref "U1") (pin "14") (pinfunction "PH1-OSC_OUT_14") (pintype "bidirectional"))
      (node (ref "X1") (pin "3") (pinfunction "CRYSTAL_2_3") (pintype "passive"))
    )
    (net (code "24") (name "/PA13") (class "Default")
      (node (ref "R9") (pin "2") (pinfunction "2_2") (pintype "passive"))
      (node (ref "U1") (pin "95") (pinfunction "PA13_95") (pintype "bidirectional"))
    )
    (net (code "25") (name "/PA14") (class "Default")
      (node (ref "R8") (pin "2") (pinfunction "2_2") (pintype "passive"))
      (node (ref "U1") (pin "96") (pinfunction "PA14_96") (pintype "bidirectional"))
    )
    (net (code "26") (name "/PB2") (class "Default")
      (node (ref "R5") (pin "2") (pinfunction "2_2") (pintype "passive"))
      (node (ref "U1") (pin "40") (pinfunction "PB2_40") (pintype "bidirectional"))
    )
    (net (code "27") (name "/PO0") (class "Default")
      (node (ref "IC1") (pin "1") (pinfunction "~{CS}_1") (pintype "passive"))
      (node (ref "R11") (pin "1") (pinfunction "1_1") (pintype "passive"))
      (node (ref "U1") (pin "64") (pinfunction "PO0_64") (pintype "bidirectional"))
    )
    (net (code "28") (name "/PO4") (class "Default")
      (node (ref "IC1") (pin "6") (pinfunction "CLK_6") (pintype "passive"))
      (node (ref "U1") (pin "53") (pinfunction "PO4_53") (pintype "bidirectional"))
    )
    (net (code "29") (name "/PP0") (class "Default")
      (node (ref "IC1") (pin "5") (pinfunction "DI_(IO0)_5") (pintype "passive"))
      (node (ref "U1") (pin "55") (pinfunction "PP0_55") (pintype "bidirectional"))
    )
    (net (code "30") (name "/PP1") (class "Default")
      (node (ref "IC1") (pin "2") (pinfunction "DO_(IO1)_2") (pintype "passive"))
      (node (ref "U1") (pin "61") (pinfunction "PP1_61") (pintype "bidirectional"))
    )
    (net (code "31") (name "/PP2") (class "Default")
      (node (ref "IC1") (pin "3") (pinfunction "~{WP_(IO2)}_3") (pintype "passive"))
      (node (ref "U1") (pin "48") (pinfunction "PP2_48") (pintype "bidirectional"))
    )
    (net (code "32") (name "/PP3") (class "Default")
      (node (ref "IC1") (pin "7") (pinfunction "~{HOLD_OR_}/RESET_(IO3)_7") (pintype "passive"))
      (node (ref "U1") (pin "49") (pinfunction "PP3_49") (pintype "bidirectional"))
    )
    (net (code "33") (name "/SRX_ETX") (class "Default")
      (node (ref "U1") (pin "92") (pinfunction "PA10_92") (pintype "bidirectional"))
      (node (ref "U2") (pin "10") (pinfunction "IO17_10") (pintype "bidirectional"))
    )
    (net (code "34") (name "/STX_ERX") (class "Default")
      (node (ref "U1") (pin "91") (pinfunction "PA9_91") (pintype "bidirectional"))
      (node (ref "U2") (pin "11") (pinfunction "IO18_11") (pintype "bidirectional"))
    )
    (net (code "35") (name "/SWDCLK") (class "Default")
      (node (ref "J4") (pin "2") (pinfunction "2_2") (pintype "passive"))
      (node (ref "R8") (pin "1") (pinfunction "1_1") (pintype "passive"))
    )
    (net (code "36") (name "/SWDIO") (class "Default")
      (node (ref "J4") (pin "4") (pinfunction "4_4") (pintype "passive"))
      (node (ref "R9") (pin "1") (pinfunction "1_1") (pintype "passive"))
    )
    (net (code "37") (name "/UART3_RX") (class "Default")
      (node (ref "P2") (pin "2") (pinfunction "2_2") (pintype "passive"))
      (node (ref "U1") (pin "66") (pinfunction "PD9_66") (pintype "bidirectional"))
    )
    (net (code "38") (name "/UART3_TX") (class "Default")
      (node (ref "P2") (pin "1") (pinfunction "1_1") (pintype "passive"))
      (node (ref "U1") (pin "65") (pinfunction "PD8_65") (pintype "bidirectional"))
    )
    (net (code "39") (name "/USB_FS_CONN_N") (class "Default")
      (node (ref "D4") (pin "1") (pinfunction "I/O1_1_1") (pintype "bidirectional"))
      (node (ref "J1") (pin "A7") (pinfunction "DN1_A7") (pintype "passive"))
      (node (ref "J1") (pin "B7") (pinfunction "DN2_B7") (pintype "passive"))
    )
    (net (code "40") (name "/USB_FS_CONN_P") (class "Default")
      (node (ref "D4") (pin "3") (pinfunction "I/O2_1_3") (pintype "bidirectional"))
      (node (ref "J1") (pin "A6") (pinfunction "DP1_A6") (pintype "passive"))
      (node (ref "J1") (pin "B6") (pinfunction "DP2_B6") (pintype "passive"))
    )
    (net (code "41") (name "/USB_FS_N") (class "Default")
      (node (ref "D4") (pin "6") (pinfunction "I/O1_2_6") (pintype "bidirectional"))
      (node (ref "U1") (pin "124") (pinfunction "PM12_124") (pintype "bidirectional"))
    )
    (net (code "42") (name "/USB_FS_P") (class "Default")
      (node (ref "D4") (pin "4") (pinfunction "I/O2_2_4") (pintype "bidirectional"))
      (node (ref "U1") (pin "125") (pinfunction "PM11_125") (pintype "bidirectional"))
    )
    (net (code "43") (name "/USB_HS_CONN_N") (class "Default")
      (node (ref "D3") (pin "1") (pinfunction "I/O1_1_1") (pintype "bidirectional"))
      (node (ref "J2") (pin "A7") (pinfunction "DN1_A7") (pintype "passive"))
      (node (ref "J2") (pin "B7") (pinfunction "DN2_B7") (pintype "passive"))
    )
    (net (code "44") (name "/USB_HS_CONN_P") (class "Default")
      (node (ref "D3") (pin "3") (pinfunction "I/O2_1_3") (pintype "bidirectional"))
      (node (ref "J2") (pin "A6") (pinfunction "DP1_A6") (pintype "passive"))
      (node (ref "J2") (pin "B6") (pinfunction "DP2_B6") (pintype "passive"))
    )
    (net (code "45") (name "/USB_HS_N") (class "Default")
      (node (ref "D3") (pin "6") (pinfunction "I/O1_2_6") (pintype "bidirectional"))
      (node (ref "U1") (pin "118") (pinfunction "PM5_118") (pintype "bidirectional"))
    )
    (net (code "46") (name "/USB_HS_P") (class "Default")
      (node (ref "D3") (pin "4") (pinfunction "I/O2_2_4") (pintype "bidirectional"))
      (node (ref "U1") (pin "119") (pinfunction "PM6_119") (pintype "bidirectional"))
    )
    (net (code "47") (name "GND") (class "Default")
      (node (ref "C1") (pin "1") (pinfunction "1_1") (pintype "passive"))
      (node (ref "C10") (pin "1") (pinfunction "1_1") (pintype "passive"))
      (node (ref "C11") (pin "1") (pinfunction "1_1") (pintype "passive"))
      (node (ref "C12") (pin "1") (pinfunction "1_1") (pintype "passive"))
      (node (ref "C13") (pin "1") (pinfunction "1_1") (pintype "passive"))
      (node (ref "C14") (pin "1") (pinfunction "1_1") (pintype "passive"))
      (node (ref "C15") (pin "1") (pinfunction "1_1") (pintype "passive"))
      (node (ref "C16") (pin "1") (pinfunction "1_1") (pintype "passive"))
      (node (ref "C17") (pin "1") (pinfunction "1_1") (pintype "passive"))
      (node (ref "C18") (pin "1") (pinfunction "1_1") (pintype "passive"))
      (node (ref "C19") (pin "1") (pinfunction "1_1") (pintype "passive"))
      (node (ref "C2") (pin "1") (pinfunction "1_1") (pintype "passive"))
      (node (ref "C20") (pin "1") (pinfunction "1_1") (pintype "passive"))
      (node (ref "C21") (pin "1") (pinfunction "1_1") (pintype "passive"))
      (node (ref "C22") (pin "1") (pinfunction "1_1") (pintype "passive"))
      (node (ref "C23") (pin "1") (pinfunction "1_1") (pintype "passive"))
      (node (ref "C24") (pin "1") (pinfunction "1_1") (pintype "passive"))
      (node (ref "C25") (pin "1") (pinfunction "1_1") (pintype "passive"))
      (node (ref "C26") (pin "2") (pinfunction "2_2") (pintype "passive"))
      (node (ref "C27") (pin "1") (pinfunction "1_1") (pintype "passive"))
      (node (ref "C28") (pin "1") (pinfunction "1_1") (pintype "passive"))
      (node (ref "C29") (pin "1") (pinfunction "1_1") (pintype "passive"))
      (node (ref "C3") (pin "1") (pinfunction "1_1") (pintype "passive"))
      (node (ref "C30") (pin "1") (pinfunction "1_1") (pintype "passive"))
      (node (ref "C31") (pin "2") (pinfunction "2_2") (pintype "passive"))
      (node (ref "C32") (pin "1") (pinfunction "1_1") (pintype "passive"))
      (node (ref "C33") (pin "1") (pinfunction "1_1") (pintype "passive"))
      (node (ref "C34") (pin "1") (pinfunction "1_1") (pintype "passive"))
      (node (ref "C35") (pin "1") (pinfunction "1_1") (pintype "passive"))
      (node (ref "C36") (pin "1") (pinfunction "1_1") (pintype "passive"))
      (node (ref "C37") (pin "2") (pinfunction "2_2") (pintype "passive"))
      (node (ref "C38") (pin "1") (pinfunction "1_1") (pintype "passive"))
      (node (ref "C39") (pin "1") (pinfunction "1_1") (pintype "passive"))
      (node (ref "C4") (pin "1") (pinfunction "1_1") (pintype "passive"))
      (node (ref "C40") (pin "2") (pinfunction "2_2") (pintype "passive"))
      (node (ref "C41") (pin "1") (pinfunction "1_1") (pintype "passive"))
      (node (ref "C42") (pin "1") (pinfunction "1_1") (pintype "passive"))
      (node (ref "C43") (pin "1") (pinfunction "1_1") (pintype "passive"))
      (node (ref "C44") (pin "1") (pinfunction "1_1") (pintype "passive"))
      (node (ref "C5") (pin "1") (pinfunction "1_1") (pintype "passive"))
      (node (ref "C6") (pin "1") (pinfunction "1_1") (pintype "passive"))
      (node (ref "C7") (pin "1") (pinfunction "1_1") (pintype "passive"))
      (node (ref "C8") (pin "1") (pinfunction "1_1") (pintype "passive"))
      (node (ref "C9") (pin "1") (pinfunction "1_1") (pintype "passive"))
      (node (ref "D3") (pin "2") (pinfunction "GND_2") (pintype "bidirectional"))
      (node (ref "D4") (pin "2") (pinfunction "GND_2") (pintype "bidirectional"))
      (node (ref "D5") (pin "3") (pinfunction "K_3") (pintype "passive"))
      (node (ref "D6") (pin "1") (pinfunction "C_1") (pintype "passive"))
      (node (ref "D7") (pin "1") (pinfunction "C_1") (pintype "passive"))
      (node (ref "IC1") (pin "4") (pinfunction "GND_4") (pintype "passive"))
      (node (ref "J1") (pin "A1B12") (pinfunction "GND_A1B12_A1B12") (pintype "passive"))
      (node (ref "J1") (pin "B1A12") (pinfunction "GND_B1A12_B1A12") (pintype "passive"))
      (node (ref "J1") (pin "S1") (pinfunction "SHIELD_1_S1") (pintype "passive"))
      (node (ref "J1") (pin "S2") (pinfunction "SHIELD_2_S2") (pintype "passive"))
      (node (ref "J1") (pin "S3") (pinfunction "SHIELD_3_S3") (pintype "passive"))
      (node (ref "J1") (pin "S4") (pinfunction "SHIELD_4_S4") (pintype "passive"))
      (node (ref "J2") (pin "A1B12") (pinfunction "GND_A1B12_A1B12") (pintype "passive"))
      (node (ref "J2") (pin "B1A12") (pinfunction "GND_B1A12_B1A12") (pintype "passive"))
      (node (ref "J2") (pin "S1") (pinfunction "SHIELD_1_S1") (pintype "passive"))
      (node (ref "J2") (pin "S2") (pinfunction "SHIELD_2_S2") (pintype "passive"))
      (node (ref "J2") (pin "S3") (pinfunction "SHIELD_3_S3") (pintype "passive"))
      (node (ref "J2") (pin "S4") (pinfunction "SHIELD_4_S4") (pintype "passive"))
      (node (ref "J3") (pin "2") (pinfunction "2_2") (pintype "passive"))
      (node (ref "J4") (pin "5") (pinfunction "5_5") (pintype "passive"))
      (node (ref "J4") (pin "6") (pinfunction "6_6") (pintype "passive"))
      (node (ref "J6") (pin "N") (pinfunction "NEG_N") (pintype "passive"))
      (node (ref "P2") (pin "3") (pinfunction "3_3") (pintype "passive"))
      (node (ref "P4") (pin "5") (pinfunction "5_5") (pintype "passive"))
      (node (ref "R1") (pin "1") (pinfunction "1_1") (pintype "passive"))
      (node (ref "R12") (pin "1") (pinfunction "1_1") (pintype "passive"))
      (node (ref "R17") (pin "1") (pinfunction "1_1") (pintype "passive"))
      (node (ref "R2") (pin "1") (pinfunction "1_1") (pintype "passive"))
      (node (ref "R3") (pin "1") (pinfunction "1_1") (pintype "passive"))
      (node (ref "R4") (pin "1") (pinfunction "1_1") (pintype "passive"))
      (node (ref "SW2") (pin "3") (pinfunction "C_3") (pintype "passive"))
      (node (ref "U1") (pin "107") (pinfunction "VSS_107") (pintype "power_in"))
      (node (ref "U1") (pin "117") (pinfunction "VSSUSB_117") (pintype "power_in"))
      (node (ref "U1") (pin "132") (pinfunction "VSS_132") (pintype "power_in"))
      (node (ref "U1") (pin "138") (pinfunction "VSS_138") (pintype "power_in"))
      (node (ref "U1") (pin "16") (pinfunction "VSS_16") (pintype "power_in"))
      (node (ref "U1") (pin "22") (pinfunction "VSSA_22") (pintype "power_in"))
      (node (ref "U1") (pin "23") (pinfunction "VREFM_23") (pintype "power_in"))
      (node (ref "U1") (pin "30") (pinfunction "VSS_30") (pintype "power_in"))
      (node (ref "U1") (pin "42") (pinfunction "VSS_42") (pintype "power_in"))
      (node (ref "U1") (pin "46") (pinfunction "VSS_46") (pintype "power_in"))
      (node (ref "U1") (pin "50") (pinfunction "VSS_50") (pintype "power_in"))
      (node (ref "U1") (pin "56") (pinfunction "VSS_56") (pintype "power_in"))
      (node (ref "U1") (pin "62") (pinfunction "VSS_62") (pintype "power_in"))
      (node (ref "U1") (pin "70") (pinfunction "VSS_70") (pintype "power_in"))
      (node (ref "U1") (pin "8") (pinfunction "VSS_8") (pintype "power_in"))
      (node (ref "U1") (pin "80") (pinfunction "VSS_80") (pintype "power_in"))
      (node (ref "U1") (pin "89") (pinfunction "VSS_89") (pintype "power_in"))
      (node (ref "U1") (pin "99") (pinfunction "VSS_99") (pintype "power_in"))
      (node (ref "U2") (pin "1") (pinfunction "GND_1") (pintype "power_in"))
      (node (ref "U2") (pin "40") (pinfunction "GND_40") (pintype "power_in"))
      (node (ref "U2") (pin "41_1") (pinfunction "GND_41_1") (pintype "power_in"))
      (node (ref "U2") (pin "41_2") (pinfunction "GND_41_2") (pintype "power_in"))
      (node (ref "U2") (pin "41_3") (pinfunction "GND_41_3") (pintype "power_in"))
      (node (ref "U2") (pin "41_4") (pinfunction "GND_41_4") (pintype "power_in"))
      (node (ref "U2") (pin "41_5") (pinfunction "GND_41_5") (pintype "power_in"))
      (node (ref "U2") (pin "41_6") (pinfunction "GND_41_6") (pintype "power_in"))
      (node (ref "U2") (pin "41_7") (pinfunction "GND_41_7") (pintype "power_in"))
      (node (ref "U2") (pin "41_8") (pinfunction "GND_41_8") (pintype "power_in"))
      (node (ref "U2") (pin "41_9") (pinfunction "GND_41_9") (pintype "power_in"))
      (node (ref "U3") (pin "2") (pinfunction "GND_2") (pintype "power_in"))
      (node (ref "U3") (pin "4") (pinfunction "GND_4") (pintype "power_in"))
      (node (ref "U4") (pin "2") (pinfunction "GND_2") (pintype "passive"))
      (node (ref "U4") (pin "8") (pinfunction "STB_8") (pintype "passive"))
    )
    (net (code "48") (name "Net-(D6-A)") (class "Default")
      (node (ref "D6") (pin "2") (pinfunction "A_2") (pintype "passive"))
      (node (ref "R5") (pin "1") (pinfunction "1_1") (pintype "passive"))
    )
    (net (code "49") (name "Net-(D7-A)") (class "Default")
      (node (ref "D7") (pin "2") (pinfunction "A_2") (pintype "passive"))
      (node (ref "R13") (pin "1") (pinfunction "1_1") (pintype "passive"))
    )
    (net (code "50") (name "VBUS") (class "Default")
      (node (ref "C5") (pin "2") (pinfunction "2_2") (pintype "passive"))
      (node (ref "D2") (pin "2") (pinfunction "A_2") (pintype "passive"))
      (node (ref "D3") (pin "5") (pinfunction "VBUS_5") (pintype "bidirectional"))
      (node (ref "J2") (pin "A4B9") (pinfunction "VBUS_A4B9_A4B9") (pintype "passive"))
      (node (ref "J2") (pin "B4A9") (pinfunction "VBUS_B4A9_B4A9") (pintype "passive"))
    )
    (net (code "51") (name "VBUS1") (class "Default")
      (node (ref "C1") (pin "2") (pinfunction "2_2") (pintype "passive"))
      (node (ref "D1") (pin "2") (pinfunction "A_2") (pintype "passive"))
      (node (ref "D4") (pin "5") (pinfunction "VBUS_5") (pintype "bidirectional"))
      (node (ref "J1") (pin "A4B9") (pinfunction "VBUS_A4B9_A4B9") (pintype "passive"))
      (node (ref "J1") (pin "B4A9") (pinfunction "VBUS_B4A9_B4A9") (pintype "passive"))
    )
    (net (code "52") (name "VCAP") (class "Default")
      (node (ref "C21") (pin "2") (pinfunction "2_2") (pintype "passive"))
      (node (ref "C22") (pin "2") (pinfunction "2_2") (pintype "passive"))
      (node (ref "C23") (pin "2") (pinfunction "2_2") (pintype "passive"))
      (node (ref "C24") (pin "2") (pinfunction "2_2") (pintype "passive"))
      (node (ref "C25") (pin "2") (pinfunction "2_2") (pintype "passive"))
      (node (ref "U1") (pin "120") (pinfunction "DVDD_120") (pintype "power_in"))
      (node (ref "U1") (pin "137") (pinfunction "VCAP4_137") (pintype "power_in"))
      (node (ref "U1") (pin "43") (pinfunction "VCAP1_43") (pintype "power_in"))
      (node (ref "U1") (pin "79") (pinfunction "VCAP2_79") (pintype "power_in"))
      (node (ref "U1") (pin "98") (pinfunction "VCAP3_98") (pintype "power_in"))
    )
    (net (code "53") (name "VCC") (class "Default")
      (node (ref "C4") (pin "2") (pinfunction "2_2") (pintype "passive"))
      (node (ref "D1") (pin "1") (pinfunction "K_1") (pintype "passive"))
      (node (ref "D2") (pin "1") (pinfunction "K_1") (pintype "passive"))
      (node (ref "P3") (pin "3") (pinfunction "3_3") (pintype "passive"))
    )
    (net (code "54") (name "VDD33") (class "Default")
      (node (ref "C10") (pin "2") (pinfunction "2_2") (pintype "passive"))
      (node (ref "C11") (pin "2") (pinfunction "2_2") (pintype "passive"))
      (node (ref "C12") (pin "2") (pinfunction "2_2") (pintype "passive"))
      (node (ref "C13") (pin "2") (pinfunction "2_2") (pintype "passive"))
      (node (ref "C14") (pin "2") (pinfunction "2_2") (pintype "passive"))
      (node (ref "C15") (pin "2") (pinfunction "2_2") (pintype "passive"))
      (node (ref "C16") (pin "2") (pinfunction "2_2") (pintype "passive"))
      (node (ref "C17") (pin "2") (pinfunction "2_2") (pintype "passive"))
      (node (ref "C18") (pin "2") (pinfunction "2_2") (pintype "passive"))
      (node (ref "C19") (pin "2") (pinfunction "2_2") (pintype "passive"))
      (node (ref "C2") (pin "2") (pinfunction "2_2") (pintype "passive"))
      (node (ref "C20") (pin "2") (pinfunction "2_2") (pintype "passive"))
      (node (ref "C3") (pin "2") (pinfunction "2_2") (pintype "passive"))
      (node (ref "C32") (pin "2") (pinfunction "2_2") (pintype "passive"))
      (node (ref "C33") (pin "2") (pinfunction "2_2") (pintype "passive"))
      (node (ref "C36") (pin "2") (pinfunction "2_2") (pintype "passive"))
      (node (ref "C38") (pin "2") (pinfunction "2_2") (pintype "passive"))
      (node (ref "C41") (pin "2") (pinfunction "2_2") (pintype "passive"))
      (node (ref "C42") (pin "2") (pinfunction "2_2") (pintype "passive"))
      (node (ref "C43") (pin "2") (pinfunction "2_2") (pintype "passive"))
      (node (ref "C6") (pin "2") (pinfunction "2_2") (pintype "passive"))
      (node (ref "C7") (pin "2") (pinfunction "2_2") (pintype "passive"))
      (node (ref "C8") (pin "2") (pinfunction "2_2") (pintype "passive"))
      (node (ref "C9") (pin "2") (pinfunction "2_2") (pintype "passive"))
      (node (ref "FB1") (pin "2") (pinfunction "2_2") (pintype "passive"))
      (node (ref "IC1") (pin "8") (pinfunction "VCC_8") (pintype "passive"))
      (node (ref "J4") (pin "7") (pinfunction "7_7") (pintype "passive"))
      (node (ref "J4") (pin "8") (pinfunction "8_8") (pintype "passive"))
      (node (ref "J5") (pin "2") (pinfunction "2_2") (pintype "passive"))
      (node (ref "R10") (pin "1") (pinfunction "1_1") (pintype "passive"))
      (node (ref "R11") (pin "2") (pinfunction "2_2") (pintype "passive"))
      (node (ref "R13") (pin "2") (pinfunction "2_2") (pintype "passive"))
      (node (ref "R15") (pin "2") (pinfunction "2_2") (pintype "passive"))
      (node (ref "R7") (pin "1") (pinfunction "1_1") (pintype "passive"))
      (node (ref "SW1") (pin "4") (pinfunction "D_4") (pintype "passive"))
      (node (ref "U1") (pin "100") (pinfunction "VDD_100") (pintype "power_in"))
      (node (ref "U1") (pin "108") (pinfunction "VDD_108") (pintype "power_in"))
      (node (ref "U1") (pin "115") (pinfunction "VDD50USB_115") (pintype "power_in"))
      (node (ref "U1") (pin "116") (pinfunction "VDD33USB_116") (pintype "power_in"))
      (node (ref "U1") (pin "123") (pinfunction "VDD_123") (pintype "power_in"))
      (node (ref "U1") (pin "133") (pinfunction "VDD_133") (pintype "power_in"))
      (node (ref "U1") (pin "139") (pinfunction "VDD_139") (pintype "power_in"))
      (node (ref "U1") (pin "17") (pinfunction "VDD_17") (pintype "power_in"))
      (node (ref "U1") (pin "3") (pinfunction "VBAT_3") (pintype "power_in"))
      (node (ref "U1") (pin "31") (pinfunction "VDD_31") (pintype "power_in"))
      (node (ref "U1") (pin "41") (pinfunction "VDD_41") (pintype "power_in"))
      (node (ref "U1") (pin "45") (pinfunction "VDDXSPI1_45") (pintype "power_in"))
      (node (ref "U1") (pin "51") (pinfunction "VDDXSPI1_51") (pintype "power_in"))
      (node (ref "U1") (pin "57") (pinfunction "VDDXSPI1_57") (pintype "power_in"))
      (node (ref "U1") (pin "63") (pinfunction "VDDXSPI1_63") (pintype "power_in"))
      (node (ref "U1") (pin "69") (pinfunction "VDD_69") (pintype "power_in"))
      (node (ref "U1") (pin "7") (pinfunction "VDD_7") (pintype "power_in"))
      (node (ref "U1") (pin "81") (pinfunction "VDD_81") (pintype "power_in"))
      (node (ref "U1") (pin "88") (pinfunction "VDD_88") (pintype "power_in"))
      (node (ref "U2") (pin "2") (pinfunction "3V3_2") (pintype "power_in"))
      (node (ref "U4") (pin "3") (pinfunction "VCC_3") (pintype "passive"))
      (node (ref "U4") (pin "5") (pinfunction "VIO_5") (pintype "passive"))
    )
    (net (code "55") (name "VDDA") (class "Default")
      (node (ref "C34") (pin "2") (pinfunction "2_2") (pintype "passive"))
      (node (ref "C35") (pin "2") (pinfunction "2_2") (pintype "passive"))
      (node (ref "FB1") (pin "1") (pinfunction "1_1") (pintype "passive"))
      (node (ref "R6") (pin "2") (pinfunction "2_2") (pintype "passive"))
      (node (ref "U1") (pin "25") (pinfunction "VDDA_25") (pintype "power_in"))
    )
    (net (code "56") (name "VREFP") (class "Default")
      (node (ref "C27") (pin "2") (pinfunction "2_2") (pintype "passive"))
      (node (ref "C28") (pin "2") (pinfunction "2_2") (pintype "passive"))
      (node (ref "R6") (pin "1") (pinfunction "1_1") (pintype "passive"))
      (node (ref "U1") (pin "24") (pinfunction "VREFP_24") (pintype "power_in"))
    )
    (net (code "57") (name "unconnected-(J1-SBU1-PadA8)") (class "Default")
      (node (ref "J1") (pin "A8") (pinfunction "SBU1_A8") (pintype "passive+no_connect"))
    )
    (net (code "58") (name "unconnected-(J1-SBU2-PadB8)") (class "Default")
      (node (ref "J1") (pin "B8") (pinfunction "SBU2_B8") (pintype "passive+no_connect"))
    )
    (net (code "59") (name "unconnected-(J2-SBU1-PadA8)") (class "Default")
      (node (ref "J2") (pin "A8") (pinfunction "SBU1_A8") (pintype "passive+no_connect"))
    )
    (net (code "60") (name "unconnected-(J2-SBU2-PadB8)") (class "Default")
      (node (ref "J2") (pin "B8") (pinfunction "SBU2_B8") (pintype "passive+no_connect"))
    )
    (net (code "61") (name "unconnected-(J4-Pad3)") (class "Default")
      (node (ref "J4") (pin "3") (pinfunction "3_3") (pintype "passive+no_connect"))
    )
    (net (code "62") (name "unconnected-(J4-Pad9)") (class "Default")
      (node (ref "J4") (pin "9") (pinfunction "9_9") (pintype "passive+no_connect"))
    )
    (net (code "63") (name "unconnected-(J4-Pad10)") (class "Default")
      (node (ref "J4") (pin "10") (pinfunction "10_10") (pintype "passive+no_connect"))
    )
    (net (code "64") (name "unconnected-(P1-Pad1)") (class "Default")
      (node (ref "P1") (pin "1") (pinfunction "1_1") (pintype "passive+no_connect"))
    )
    (net (code "65") (name "unconnected-(P1-Pad2)") (class "Default")
      (node (ref "P1") (pin "2") (pinfunction "2_2") (pintype "passive+no_connect"))
    )
    (net (code "66") (name "unconnected-(P1-Pad3)") (class "Default")
      (node (ref "P1") (pin "3") (pinfunction "3_3") (pintype "passive+no_connect"))
    )
    (net (code "67") (name "unconnected-(P1-Pad4)") (class "Default")
      (node (ref "P1") (pin "4") (pinfunction "4_4") (pintype "passive+no_connect"))
    )
    (net (code "68") (name "unconnected-(P1-Pad5)") (class "Default")
      (node (ref "P1") (pin "5") (pinfunction "5_5") (pintype "passive+no_connect"))
    )
    (net (code "69") (name "unconnected-(SW1-A-Pad1)") (class "Default")
      (node (ref "SW1") (pin "1") (pinfunction "A_1") (pintype "passive+no_connect"))
    )
    (net (code "70") (name "unconnected-(SW1-C-Pad3)") (class "Default")
      (node (ref "SW1") (pin "3") (pinfunction "C_3") (pintype "passive+no_connect"))
    )
    (net (code "71") (name "unconnected-(SW2-B-Pad2)") (class "Default")
      (node (ref "SW2") (pin "2") (pinfunction "B_2") (pintype "passive+no_connect"))
    )
    (net (code "72") (name "unconnected-(SW2-D-Pad4)") (class "Default")
      (node (ref "SW2") (pin "4") (pinfunction "D_4") (pintype "passive+no_connect"))
    )
    (net (code "73") (name "unconnected-(U1A-PA0-Pad26)") (class "Default")
      (node (ref "U1") (pin "26") (pinfunction "PA0_26") (pintype "bidirectional+no_connect"))
    )
    (net (code "74") (name "unconnected-(U1A-PA1-Pad27)") (class "Default")
      (node (ref "U1") (pin "27") (pinfunction "PA1_27") (pintype "bidirectional+no_connect"))
    )
    (net (code "75") (name "unconnected-(U1A-PA2-Pad28)") (class "Default")
      (node (ref "U1") (pin "28") (pinfunction "PA2_28") (pintype "bidirectional+no_connect"))
    )
    (net (code "76") (name "unconnected-(U1A-PA3-Pad29)") (class "Default")
      (node (ref "U1") (pin "29") (pinfunction "PA3_29") (pintype "bidirectional+no_connect"))
    )
    (net (code "77") (name "unconnected-(U1A-PA4-Pad32)") (class "Default")
      (node (ref "U1") (pin "32") (pinfunction "PA4_32") (pintype "bidirectional+no_connect"))
    )
    (net (code "78") (name "unconnected-(U1A-PA5-Pad33)") (class "Default")
      (node (ref "U1") (pin "33") (pinfunction "PA5_33") (pintype "bidirectional+no_connect"))
    )
    (net (code "79") (name "unconnected-(U1A-PA6-Pad34)") (class "Default")
      (node (ref "U1") (pin "34") (pinfunction "PA6_34") (pintype "bidirectional+no_connect"))
    )
    (net (code "80") (name "unconnected-(U1A-PA7-Pad35)") (class "Default")
      (node (ref "U1") (pin "35") (pinfunction "PA7_35") (pintype "bidirectional+no_connect"))
    )
    (net (code "81") (name "unconnected-(U1A-PA8-Pad90)") (class "Default")
      (node (ref "U1") (pin "90") (pinfunction "PA8_90") (pintype "bidirectional+no_connect"))
    )
    (net (code "82") (name "unconnected-(U1A-PA11-Pad93)") (class "Default")
      (node (ref "U1") (pin "93") (pinfunction "PA11_93") (pintype "bidirectional+no_connect"))
    )
    (net (code "83") (name "unconnected-(U1A-PA12-Pad94)") (class "Default")
      (node (ref "U1") (pin "94") (pinfunction "PA12_94") (pintype "bidirectional+no_connect"))
    )
    (net (code "84") (name "unconnected-(U1A-PA15-Pad97)") (class "Default")
      (node (ref "U1") (pin "97") (pinfunction "PA15_97") (pintype "bidirectional+no_connect"))
    )
    (net (code "85") (name "unconnected-(U1A-PB0-Pad38)") (class "Default")
      (node (ref "U1") (pin "38") (pinfunction "PB0_38") (pintype "bidirectional+no_connect"))
    )
    (net (code "86") (name "unconnected-(U1A-PB1-Pad39)") (class "Default")
      (node (ref "U1") (pin "39") (pinfunction "PB1_39") (pintype "bidirectional+no_connect"))
    )
    (net (code "87") (name "unconnected-(U1A-PB3-Pad134)") (class "Default")
      (node (ref "U1") (pin "134") (pinfunction "PB3_134") (pintype "bidirectional+no_connect"))
    )
    (net (code "88") (name "unconnected-(U1A-PB4-Pad135)") (class "Default")
      (node (ref "U1") (pin "135") (pinfunction "PB4_135") (pintype "bidirectional+no_connect"))
    )
    (net (code "89") (name "unconnected-(U1A-PB6-Pad143)") (class "Default")
      (node (ref "U1") (pin "143") (pinfunction "PB6_143") (pintype "bidirectional+no_connect"))
    )
    (net (code "90") (name "unconnected-(U1A-PB7-Pad144)") (class "Default")
      (node (ref "U1") (pin "144") (pinfunction "PB7_144") (pintype "bidirectional+no_connect"))
    )
    (net (code "91") (name "unconnected-(U1A-PB8-Pad1)") (class "Default")
      (node (ref "U1") (pin "1") (pinfunction "PB8_1") (pintype "bidirectional+no_connect"))
    )
    (net (code "92") (name "unconnected-(U1A-PB9-Pad2)") (class "Default")
      (node (ref "U1") (pin "2") (pinfunction "PB9_2") (pintype "bidirectional+no_connect"))
    )
    (net (code "93") (name "unconnected-(U1A-PB10-Pad73)") (class "Default")
      (node (ref "U1") (pin "73") (pinfunction "PB10_73") (pintype "bidirectional"))
    )
    (net (code "94") (name "unconnected-(U1A-PB11-Pad74)") (class "Default")
      (node (ref "U1") (pin "74") (pinfunction "PB11_74") (pintype "bidirectional+no_connect"))
    )
    (net (code "95") (name "unconnected-(U1A-PB12-Pad75)") (class "Default")
      (node (ref "U1") (pin "75") (pinfunction "PB12_75") (pintype "bidirectional+no_connect"))
    )
    (net (code "96") (name "unconnected-(U1A-PB13-Pad76)") (class "Default")
      (node (ref "U1") (pin "76") (pinfunction "PB13_76") (pintype "bidirectional+no_connect"))
    )
    (net (code "97") (name "unconnected-(U1A-PB14-Pad77)") (class "Default")
      (node (ref "U1") (pin "77") (pinfunction "PB14_77") (pintype "bidirectional+no_connect"))
    )
    (net (code "98") (name "unconnected-(U1A-PB15-Pad78)") (class "Default")
      (node (ref "U1") (pin "78") (pinfunction "PB15_78") (pintype "bidirectional+no_connect"))
    )
    (net (code "99") (name "unconnected-(U1A-PC0-Pad18)") (class "Default")
      (node (ref "U1") (pin "18") (pinfunction "PC0_18") (pintype "bidirectional+no_connect"))
    )
    (net (code "100") (name "unconnected-(U1A-PC1-Pad19)") (class "Default")
      (node (ref "U1") (pin "19") (pinfunction "PC1_19") (pintype "bidirectional+no_connect"))
    )
    (net (code "101") (name "unconnected-(U1A-PC2-Pad20)") (class "Default")
      (node (ref "U1") (pin "20") (pinfunction "PC2_20") (pintype "bidirectional+no_connect"))
    )
    (net (code "102") (name "unconnected-(U1A-PC3-Pad21)") (class "Default")
      (node (ref "U1") (pin "21") (pinfunction "PC3_21") (pintype "bidirectional+no_connect"))
    )
    (net (code "103") (name "unconnected-(U1A-PC4-Pad36)") (class "Default")
      (node (ref "U1") (pin "36") (pinfunction "PC4_36") (pintype "bidirectional+no_connect"))
    )
    (net (code "104") (name "unconnected-(U1A-PC5-Pad37)") (class "Default")
      (node (ref "U1") (pin "37") (pinfunction "PC5_37") (pintype "bidirectional+no_connect"))
    )
    (net (code "105") (name "unconnected-(U1A-PC6-Pad84)") (class "Default")
      (node (ref "U1") (pin "84") (pinfunction "PC6_84") (pintype "bidirectional+no_connect"))
    )
    (net (code "106") (name "unconnected-(U1A-PC7-Pad85)") (class "Default")
      (node (ref "U1") (pin "85") (pinfunction "PC7_85") (pintype "bidirectional+no_connect"))
    )
    (net (code "107") (name "unconnected-(U1A-PC8-Pad86)") (class "Default")
      (node (ref "U1") (pin "86") (pinfunction "PC8_86") (pintype "bidirectional+no_connect"))
    )
    (net (code "108") (name "unconnected-(U1A-PC9-Pad87)") (class "Default")
      (node (ref "U1") (pin "87") (pinfunction "PC9_87") (pintype "bidirectional+no_connect"))
    )
    (net (code "109") (name "unconnected-(U1A-PC10-Pad101)") (class "Default")
      (node (ref "U1") (pin "101") (pinfunction "PC10_101") (pintype "bidirectional+no_connect"))
    )
    (net (code "110") (name "unconnected-(U1A-PC11-Pad102)") (class "Default")
      (node (ref "U1") (pin "102") (pinfunction "PC11_102") (pintype "bidirectional+no_connect"))
    )
    (net (code "111") (name "unconnected-(U1A-PC12-Pad103)") (class "Default")
      (node (ref "U1") (pin "103") (pinfunction "PC12_103") (pintype "bidirectional+no_connect"))
    )
    (net (code "112") (name "unconnected-(U1A-PC13-Pad4)") (class "Default")
      (node (ref "U1") (pin "4") (pinfunction "PC13_4") (pintype "bidirectional+no_connect"))
    )
    (net (code "113") (name "unconnected-(U1A-PD2-Pad106)") (class "Default")
      (node (ref "U1") (pin "106") (pinfunction "PD2_106") (pintype "bidirectional+no_connect"))
    )
    (net (code "114") (name "unconnected-(U1A-PD3-Pad109)") (class "Default")
      (node (ref "U1") (pin "109") (pinfunction "PD3_109") (pintype "bidirectional+no_connect"))
    )
    (net (code "115") (name "unconnected-(U1A-PD4-Pad110)") (class "Default")
      (node (ref "U1") (pin "110") (pinfunction "PD4_110") (pintype "bidirectional+no_connect"))
    )
    (net (code "116") (name "unconnected-(U1A-PD5-Pad129)") (class "Default")
      (node (ref "U1") (pin "129") (pinfunction "PD5_129") (pintype "bidirectional+no_connect"))
    )
    (net (code "117") (name "unconnected-(U1A-PD6-Pad130)") (class "Default")
      (node (ref "U1") (pin "130") (pinfunction "PD6_130") (pintype "bidirectional+no_connect"))
    )
    (net (code "118") (name "unconnected-(U1A-PD7-Pad131)") (class "Default")
      (node (ref "U1") (pin "131") (pinfunction "PD7_131") (pintype "bidirectional+no_connect"))
    )
    (net (code "119") (name "unconnected-(U1A-PD10-Pad67)") (class "Default")
      (node (ref "U1") (pin "67") (pinfunction "PD10_67") (pintype "bidirectional+no_connect"))
    )
    (net (code "120") (name "unconnected-(U1A-PD11-Pad68)") (class "Default")
      (node (ref "U1") (pin "68") (pinfunction "PD11_68") (pintype "bidirectional+no_connect"))
    )
    (net (code "121") (name "unconnected-(U1A-PD12-Pad71)") (class "Default")
      (node (ref "U1") (pin "71") (pinfunction "PD12_71") (pintype "bidirectional+no_connect"))
    )
    (net (code "122") (name "unconnected-(U1A-PD13-Pad72)") (class "Default")
      (node (ref "U1") (pin "72") (pinfunction "PD13_72") (pintype "bidirectional+no_connect"))
    )
    (net (code "123") (name "unconnected-(U1A-PD14-Pad82)") (class "Default")
      (node (ref "U1") (pin "82") (pinfunction "PD14_82") (pintype "bidirectional+no_connect"))
    )
    (net (code "124") (name "unconnected-(U1A-PD15-Pad83)") (class "Default")
      (node (ref "U1") (pin "83") (pinfunction "PD15_83") (pintype "bidirectional+no_connect"))
    )
    (net (code "125") (name "unconnected-(U1B-PE0-Pad140)") (class "Default")
      (node (ref "U1") (pin "140") (pinfunction "PE0_140") (pintype "bidirectional+no_connect"))
    )
    (net (code "126") (name "unconnected-(U1B-PE1-Pad141)") (class "Default")
      (node (ref "U1") (pin "141") (pinfunction "PE1_141") (pintype "bidirectional+no_connect"))
    )
    (net (code "127") (name "unconnected-(U1B-PE2-Pad142)") (class "Default")
      (node (ref "U1") (pin "142") (pinfunction "PE2_142") (pintype "bidirectional+no_connect"))
    )
    (net (code "128") (name "unconnected-(U1B-PE3-Pad9)") (class "Default")
      (node (ref "U1") (pin "9") (pinfunction "PE3_9") (pintype "bidirectional+no_connect"))
    )
    (net (code "129") (name "unconnected-(U1B-PE4-Pad10)") (class "Default")
      (node (ref "U1") (pin "10") (pinfunction "PE4_10") (pintype "bidirectional+no_connect"))
    )
    (net (code "130") (name "unconnected-(U1B-PE5-Pad11)") (class "Default")
      (node (ref "U1") (pin "11") (pinfunction "PE5_11") (pintype "bidirectional+no_connect"))
    )
    (net (code "131") (name "unconnected-(U1B-PE6-Pad12)") (class "Default")
      (node (ref "U1") (pin "12") (pinfunction "PE6_12") (pintype "bidirectional+no_connect"))
    )
    (net (code "132") (name "unconnected-(U1B-PM0-Pad111)") (class "Default")
      (node (ref "U1") (pin "111") (pinfunction "PM0_111") (pintype "bidirectional+no_connect"))
    )
    (net (code "133") (name "unconnected-(U1B-PM1-Pad112)") (class "Default")
      (node (ref "U1") (pin "112") (pinfunction "PM1_112") (pintype "bidirectional+no_connect"))
    )
    (net (code "134") (name "unconnected-(U1B-PM2-Pad113)") (class "Default")
      (node (ref "U1") (pin "113") (pinfunction "PM2_113") (pintype "bidirectional+no_connect"))
    )
    (net (code "135") (name "unconnected-(U1B-PM3-Pad114)") (class "Default")
      (node (ref "U1") (pin "114") (pinfunction "PM3_114") (pintype "bidirectional+no_connect"))
    )
    (net (code "136") (name "unconnected-(U1B-PM8-Pad121)") (class "Default")
      (node (ref "U1") (pin "121") (pinfunction "PM8_121") (pintype "bidirectional+no_connect"))
    )
    (net (code "137") (name "unconnected-(U1B-PM9-Pad122)") (class "Default")
      (node (ref "U1") (pin "122") (pinfunction "PM9_122") (pintype "bidirectional+no_connect"))
    )
    (net (code "138") (name "unconnected-(U1B-PM13-Pad127)") (class "Default")
      (node (ref "U1") (pin "127") (pinfunction "PM13_127") (pintype "bidirectional+no_connect"))
    )
    (net (code "139") (name "unconnected-(U1B-PM14-Pad126)") (class "Default")
      (node (ref "U1") (pin "126") (pinfunction "PM14_126") (pintype "bidirectional+no_connect"))
    )
    (net (code "140") (name "unconnected-(U1B-PO1-Pad44)") (class "Default")
      (node (ref "U1") (pin "44") (pinfunction "PO1_44") (pintype "bidirectional+no_connect"))
    )
    (net (code "141") (name "unconnected-(U1B-PO2-Pad59)") (class "Default")
      (node (ref "U1") (pin "59") (pinfunction "PO2_59") (pintype "bidirectional+no_connect"))
    )
    (net (code "142") (name "unconnected-(U1B-PO5-Pad52)") (class "Default")
      (node (ref "U1") (pin "52") (pinfunction "PO5_52") (pintype "bidirectional+no_connect"))
    )
    (net (code "143") (name "unconnected-(U1B-PP4-Pad47)") (class "Default")
      (node (ref "U1") (pin "47") (pinfunction "PP4_47") (pintype "bidirectional+no_connect"))
    )
    (net (code "144") (name "unconnected-(U1B-PP5-Pad54)") (class "Default")
      (node (ref "U1") (pin "54") (pinfunction "PP5_54") (pintype "bidirectional+no_connect"))
    )
    (net (code "145") (name "unconnected-(U1B-PP6-Pad58)") (class "Default")
      (node (ref "U1") (pin "58") (pinfunction "PP6_58") (pintype "bidirectional+no_connect"))
    )
    (net (code "146") (name "unconnected-(U1B-PP7-Pad60)") (class "Default")
      (node (ref "U1") (pin "60") (pinfunction "PP7_60") (pintype "bidirectional+no_connect"))
    )
    (net (code "147") (name "unconnected-(U2-IO1-Pad39)") (class "Default")
      (node (ref "U2") (pin "39") (pinfunction "IO1_39") (pintype "bidirectional+no_connect"))
    )
    (net (code "148") (name "unconnected-(U2-IO2-Pad38)") (class "Default")
      (node (ref "U2") (pin "38") (pinfunction "IO2_38") (pintype "bidirectional+no_connect"))
    )
    (net (code "149") (name "unconnected-(U2-IO3-Pad15)") (class "Default")
      (node (ref "U2") (pin "15") (pinfunction "IO3_15") (pintype "bidirectional+no_connect"))
    )
    (net (code "150") (name "unconnected-(U2-IO4-Pad4)") (class "Default")
      (node (ref "U2") (pin "4") (pinfunction "IO4_4") (pintype "bidirectional+no_connect"))
    )
    (net (code "151") (name "unconnected-(U2-IO5-Pad5)") (class "Default")
      (node (ref "U2") (pin "5") (pinfunction "IO5_5") (pintype "bidirectional+no_connect"))
    )
    (net (code "152") (name "unconnected-(U2-IO6-Pad6)") (class "Default")
      (node (ref "U2") (pin "6") (pinfunction "IO6_6") (pintype "bidirectional+no_connect"))
    )
    (net (code "153") (name "unconnected-(U2-IO7-Pad7)") (class "Default")
      (node (ref "U2") (pin "7") (pinfunction "IO7_7") (pintype "bidirectional+no_connect"))
    )
    (net (code "154") (name "unconnected-(U2-IO8-Pad12)") (class "Default")
      (node (ref "U2") (pin "12") (pinfunction "IO8_12") (pintype "bidirectional+no_connect"))
    )
    (net (code "155") (name "unconnected-(U2-IO9-Pad17)") (class "Default")
      (node (ref "U2") (pin "17") (pinfunction "IO9_17") (pintype "bidirectional+no_connect"))
    )
    (net (code "156") (name "unconnected-(U2-IO10-Pad18)") (class "Default")
      (node (ref "U2") (pin "18") (pinfunction "IO10_18") (pintype "bidirectional+no_connect"))
    )
    (net (code "157") (name "unconnected-(U2-IO11-Pad19)") (class "Default")
      (node (ref "U2") (pin "19") (pinfunction "IO11_19") (pintype "bidirectional+no_connect"))
    )
    (net (code "158") (name "unconnected-(U2-IO12-Pad20)") (class "Default")
      (node (ref "U2") (pin "20") (pinfunction "IO12_20") (pintype "bidirectional+no_connect"))
    )
    (net (code "159") (name "unconnected-(U2-IO13-Pad21)") (class "Default")
      (node (ref "U2") (pin "21") (pinfunction "IO13_21") (pintype "bidirectional+no_connect"))
    )
    (net (code "160") (name "unconnected-(U2-IO14-Pad22)") (class "Default")
      (node (ref "U2") (pin "22") (pinfunction "IO14_22") (pintype "bidirectional+no_connect"))
    )
    (net (code "161") (name "unconnected-(U2-IO15-Pad8)") (class "Default")
      (node (ref "U2") (pin "8") (pinfunction "IO15_8") (pintype "bidirectional+no_connect"))
    )
    (net (code "162") (name "unconnected-(U2-IO16-Pad9)") (class "Default")
      (node (ref "U2") (pin "9") (pinfunction "IO16_9") (pintype "bidirectional+no_connect"))
    )
    (net (code "163") (name "unconnected-(U2-IO19-Pad13)") (class "Default")
      (node (ref "U2") (pin "13") (pinfunction "IO19_13") (pintype "bidirectional+no_connect"))
    )
    (net (code "164") (name "unconnected-(U2-IO20-Pad14)") (class "Default")
      (node (ref "U2") (pin "14") (pinfunction "IO20_14") (pintype "bidirectional+no_connect"))
    )
    (net (code "165") (name "unconnected-(U2-IO21-Pad23)") (class "Default")
      (node (ref "U2") (pin "23") (pinfunction "IO21_23") (pintype "bidirectional+no_connect"))
    )
    (net (code "166") (name "unconnected-(U2-IO35-Pad28)") (class "Default")
      (node (ref "U2") (pin "28") (pinfunction "IO35_28") (pintype "bidirectional+no_connect"))
    )
    (net (code "167") (name "unconnected-(U2-IO36-Pad29)") (class "Default")
      (node (ref "U2") (pin "29") (pinfunction "IO36_29") (pintype "bidirectional+no_connect"))
    )
    (net (code "168") (name "unconnected-(U2-IO37-Pad30)") (class "Default")
      (node (ref "U2") (pin "30") (pinfunction "IO37_30") (pintype "bidirectional+no_connect"))
    )
    (net (code "169") (name "unconnected-(U2-IO38-Pad31)") (class "Default")
      (node (ref "U2") (pin "31") (pinfunction "IO38_31") (pintype "bidirectional+no_connect"))
    )
    (net (code "170") (name "unconnected-(U2-IO39-Pad32)") (class "Default")
      (node (ref "U2") (pin "32") (pinfunction "IO39_32") (pintype "bidirectional+no_connect"))
    )
    (net (code "171") (name "unconnected-(U2-IO40-Pad33)") (class "Default")
      (node (ref "U2") (pin "33") (pinfunction "IO40_33") (pintype "bidirectional+no_connect"))
    )
    (net (code "172") (name "unconnected-(U2-IO41-Pad34)") (class "Default")
      (node (ref "U2") (pin "34") (pinfunction "IO41_34") (pintype "bidirectional+no_connect"))
    )
    (net (code "173") (name "unconnected-(U2-IO42-Pad35)") (class "Default")
      (node (ref "U2") (pin "35") (pinfunction "IO42_35") (pintype "bidirectional+no_connect"))
    )
    (net (code "174") (name "unconnected-(U2-IO45-Pad26)") (class "Default")
      (node (ref "U2") (pin "26") (pinfunction "IO45_26") (pintype "bidirectional+no_connect"))
    )
    (net (code "175") (name "unconnected-(U2-IO46-Pad16)") (class "Default")
      (node (ref "U2") (pin "16") (pinfunction "IO46_16") (pintype "bidirectional+no_connect"))
    )
    (net (code "176") (name "unconnected-(U2-IO47-Pad24)") (class "Default")
      (node (ref "U2") (pin "24") (pinfunction "IO47_24") (pintype "bidirectional+no_connect"))
    )
    (net (code "177") (name "unconnected-(U2-IO48-Pad25)") (class "Default")
      (node (ref "U2") (pin "25") (pinfunction "IO48_25") (pintype "bidirectional+no_connect"))
    )
  )
)
